# transponder-9_3_0.net
KiCad netlist of a schematic drawn in EAGLE
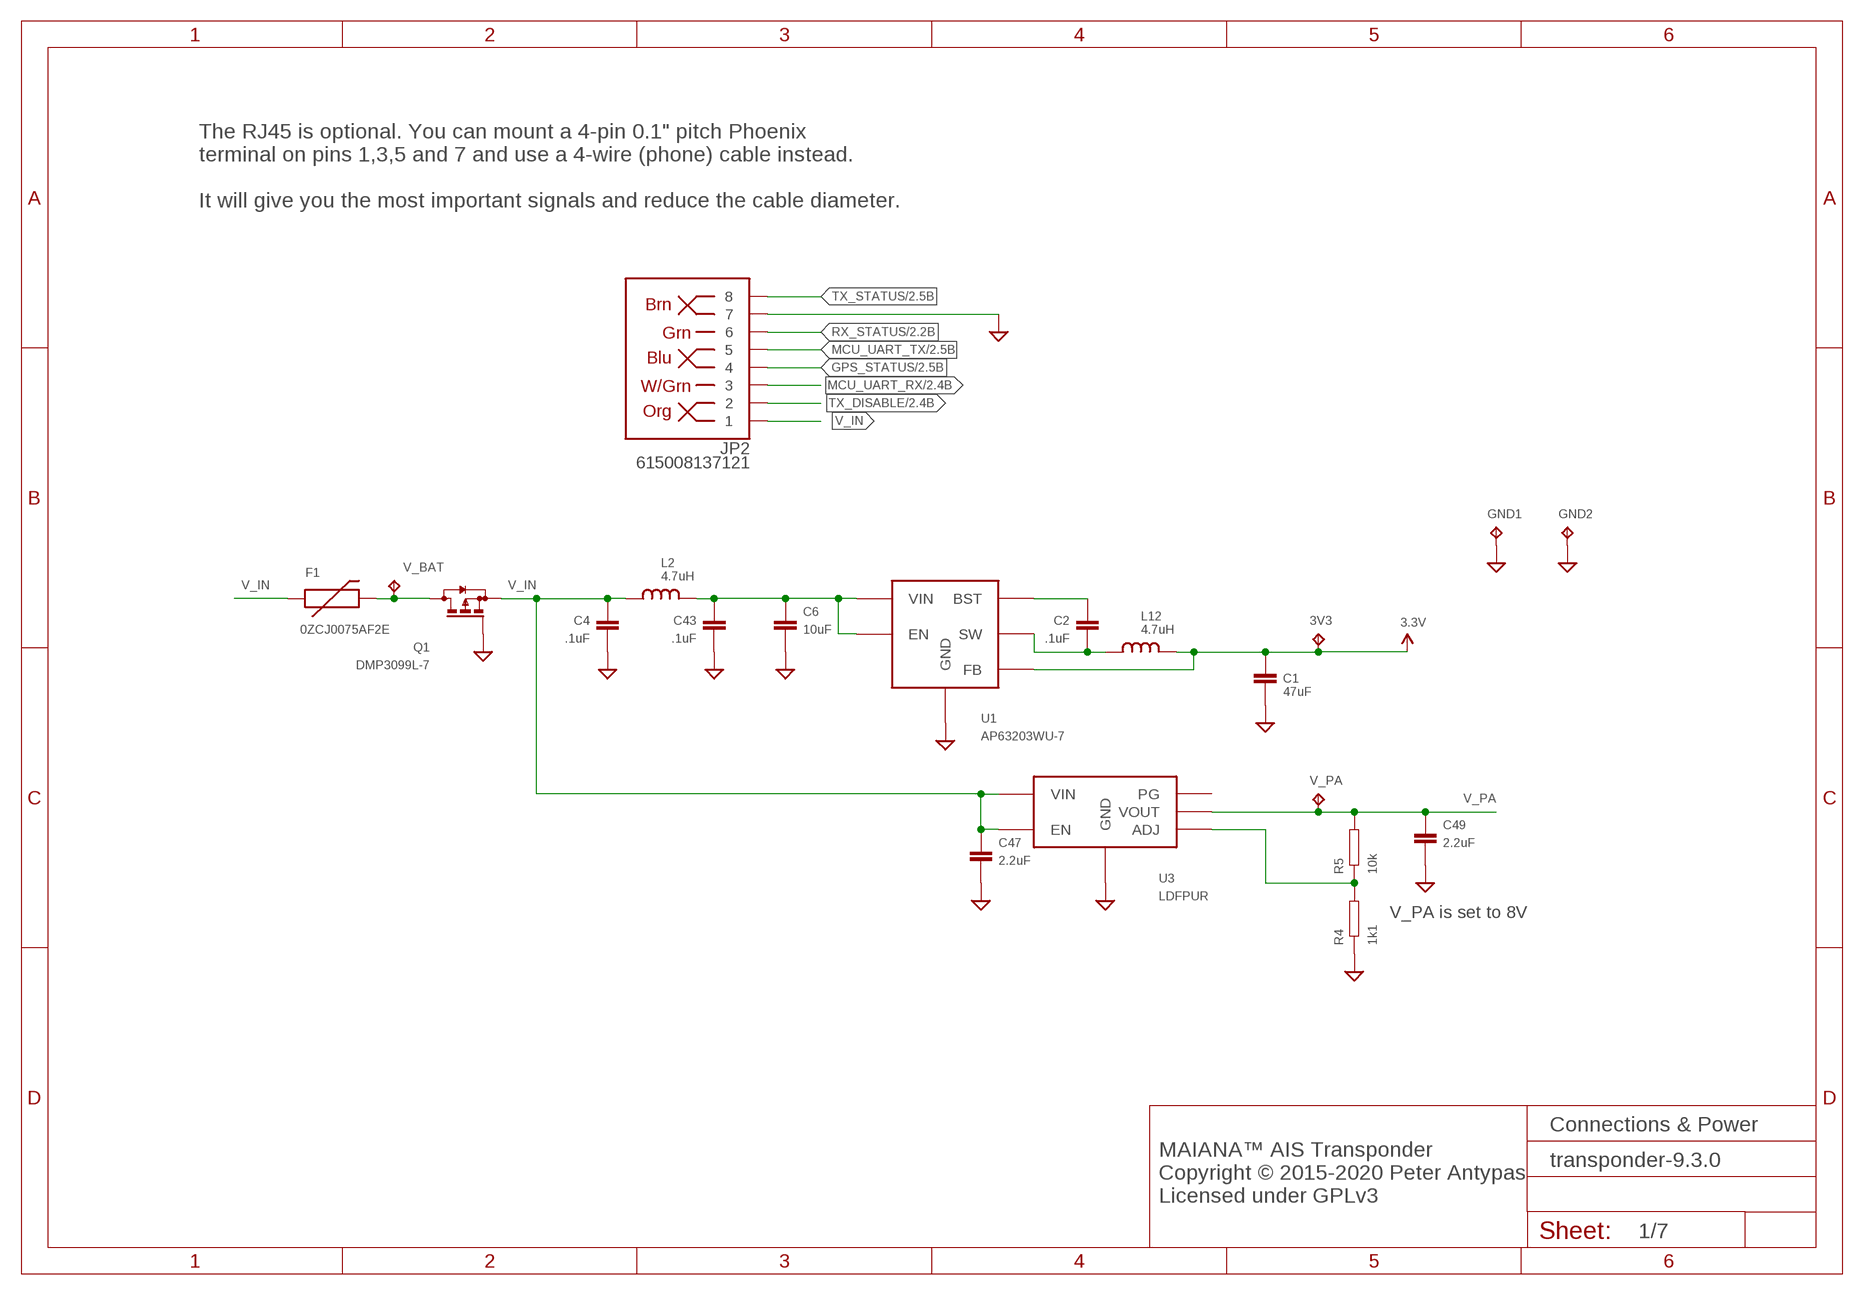
[diagram p0: schematic, sheet 1]
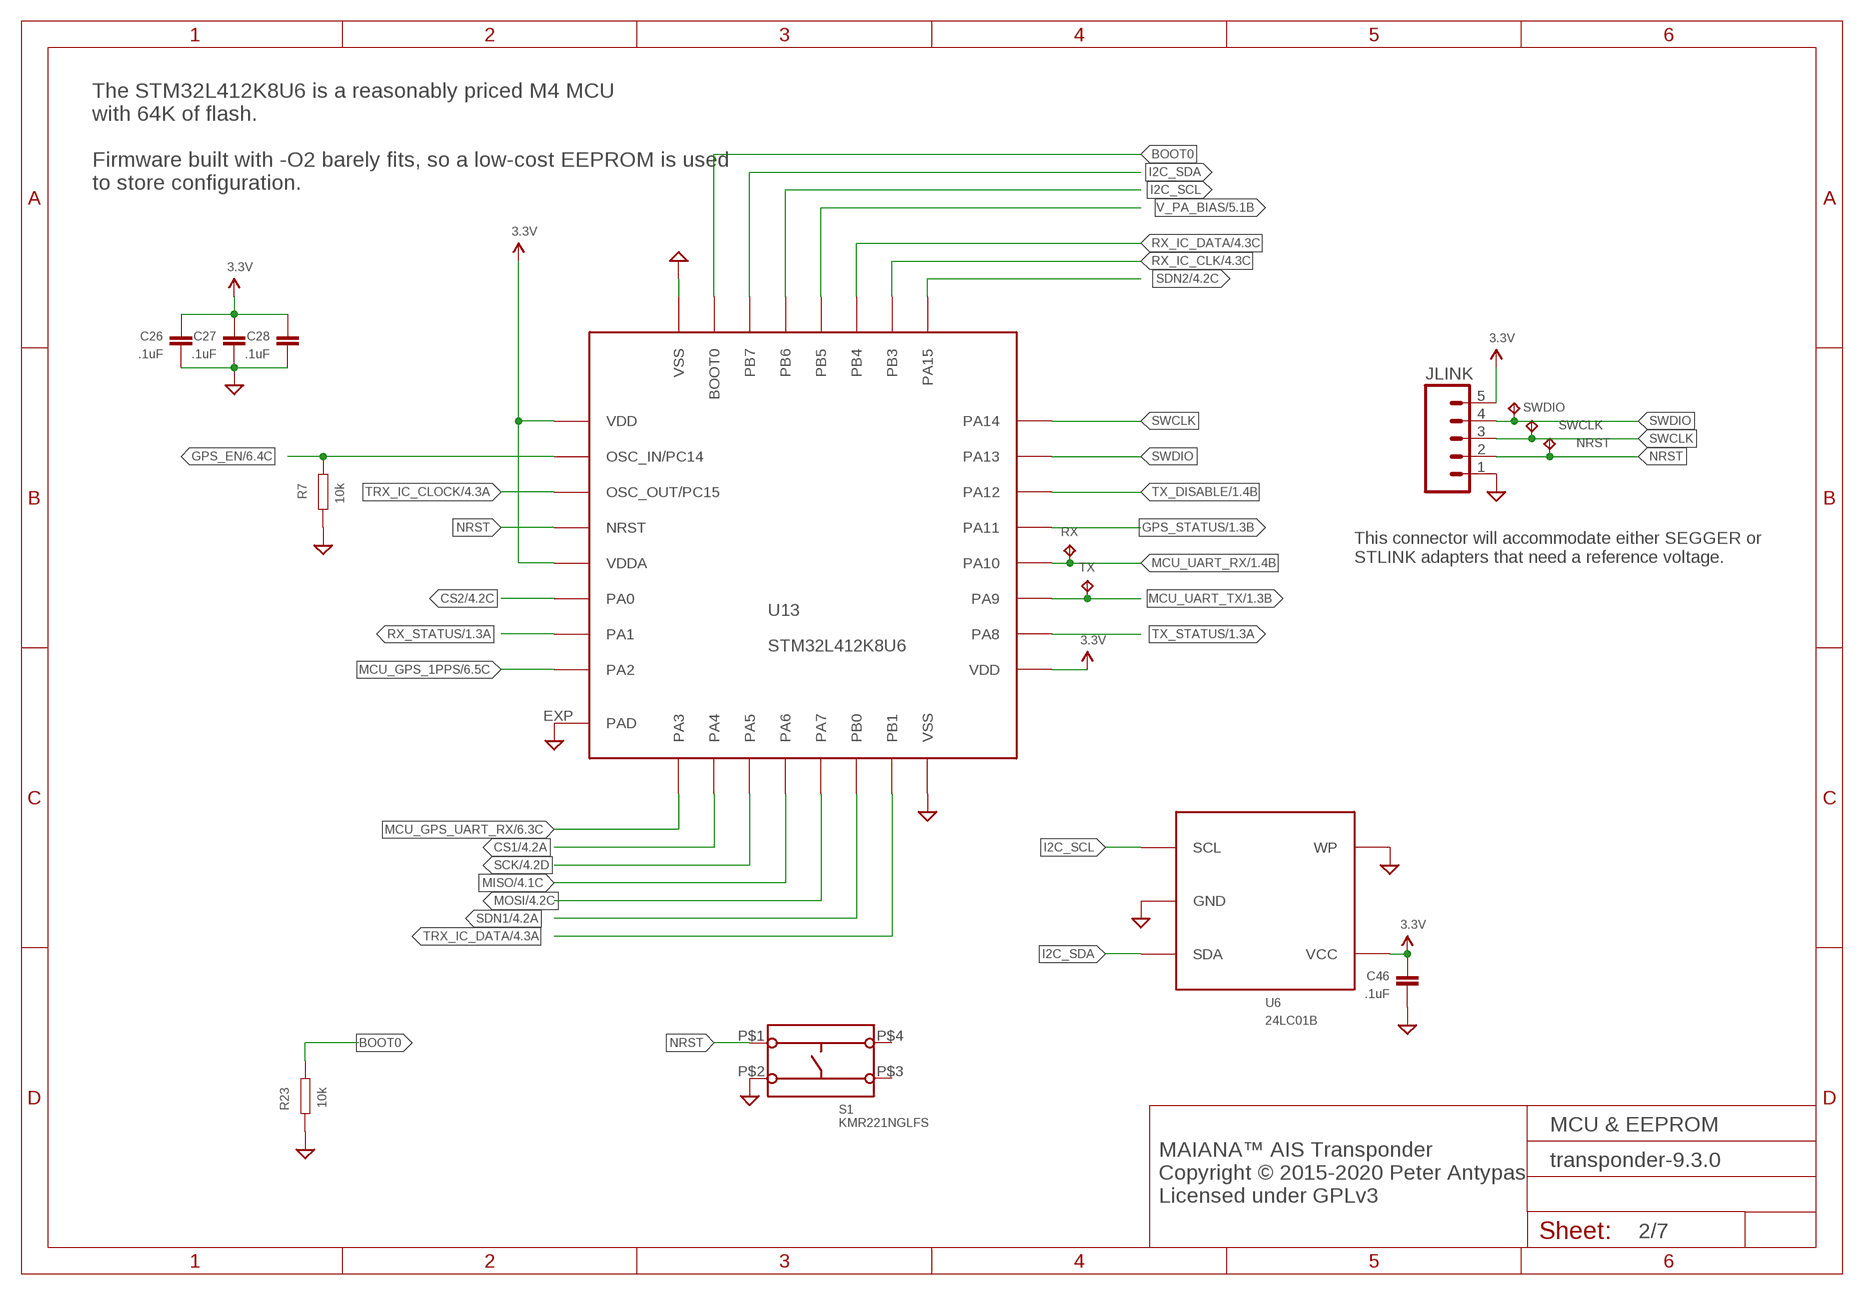
[diagram p1: schematic, sheet 2]
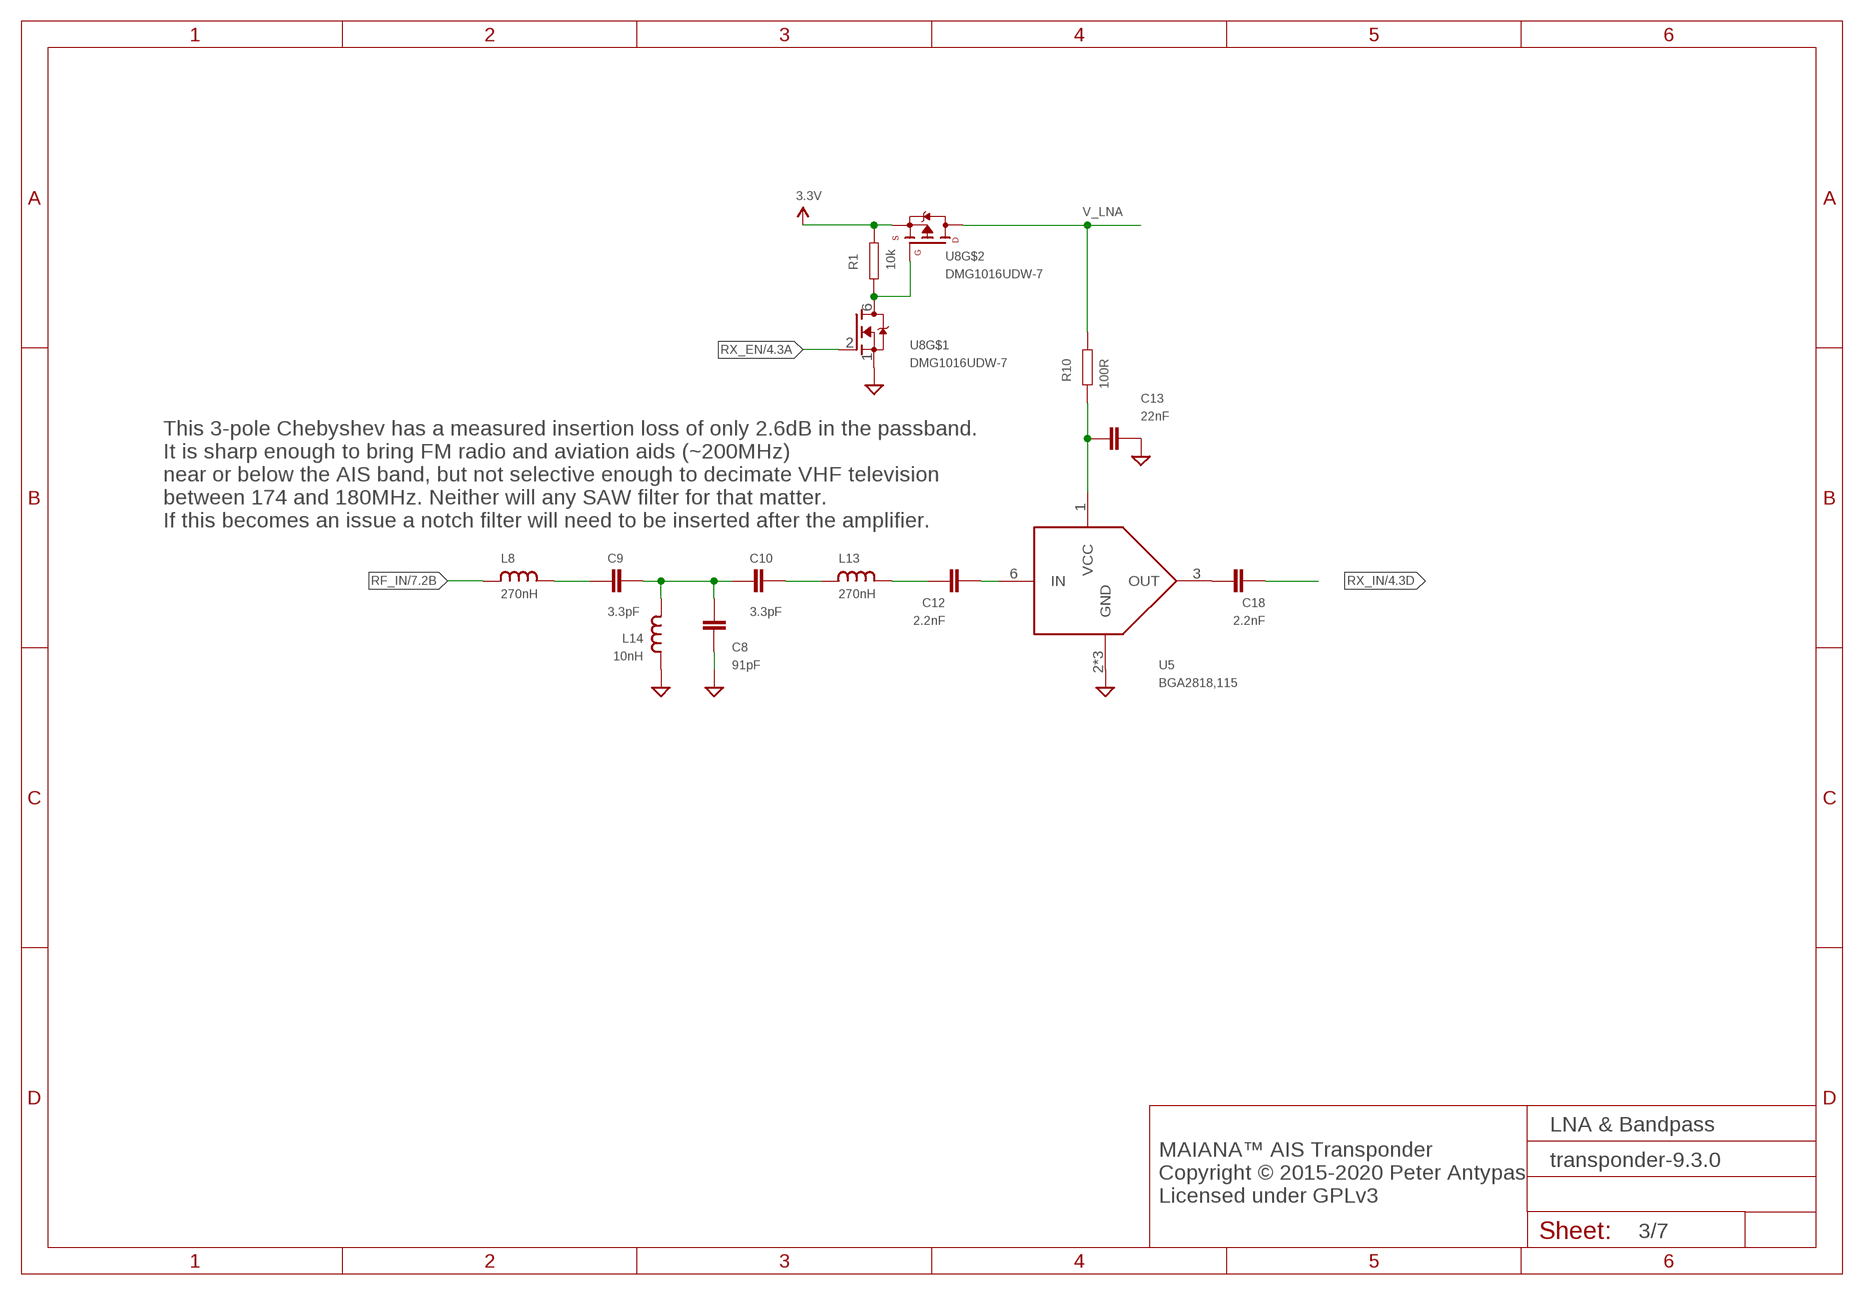
[diagram p2: schematic, sheet 3]
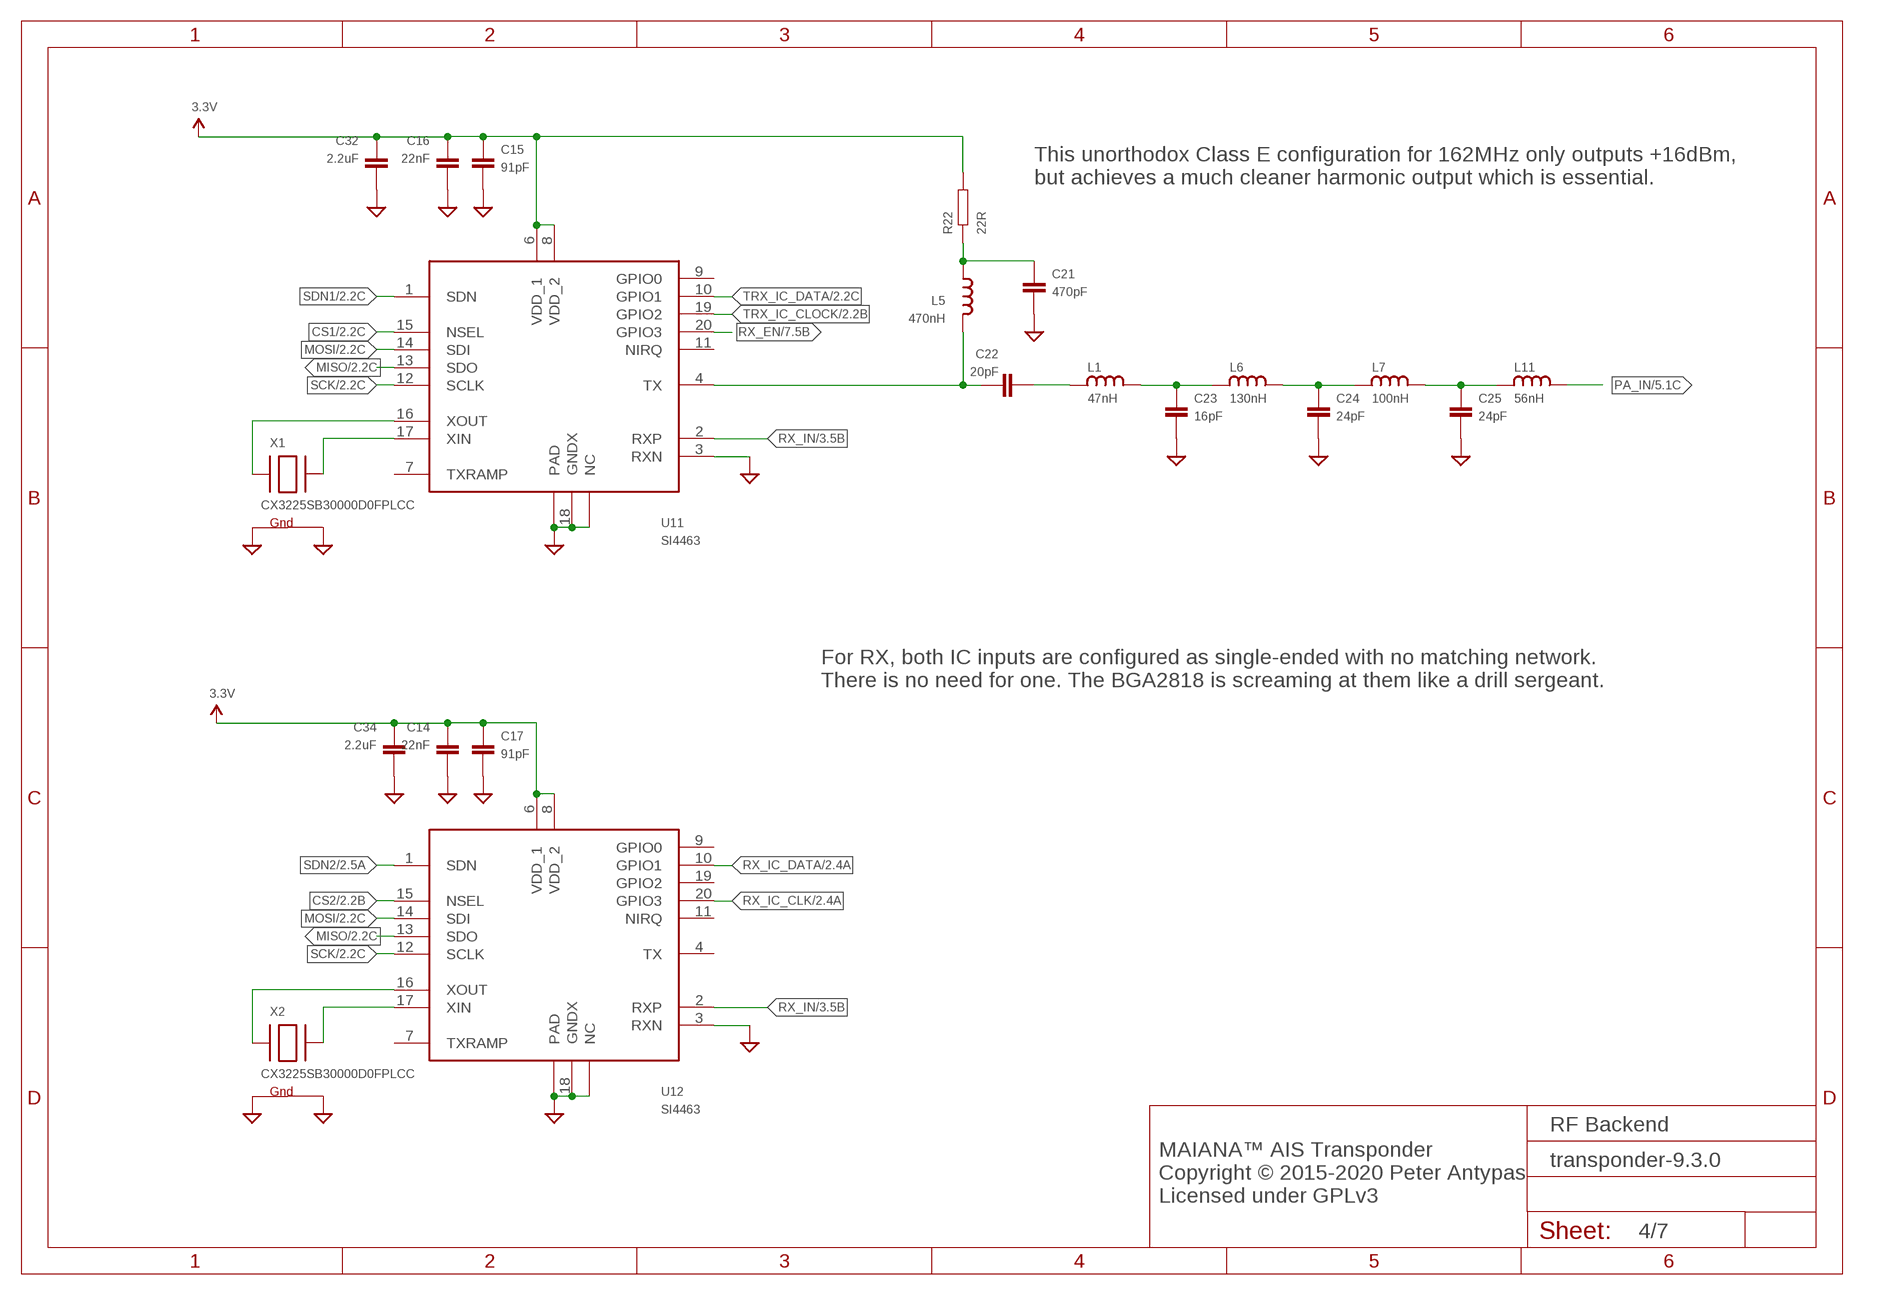
[diagram p3: schematic, sheet 4]
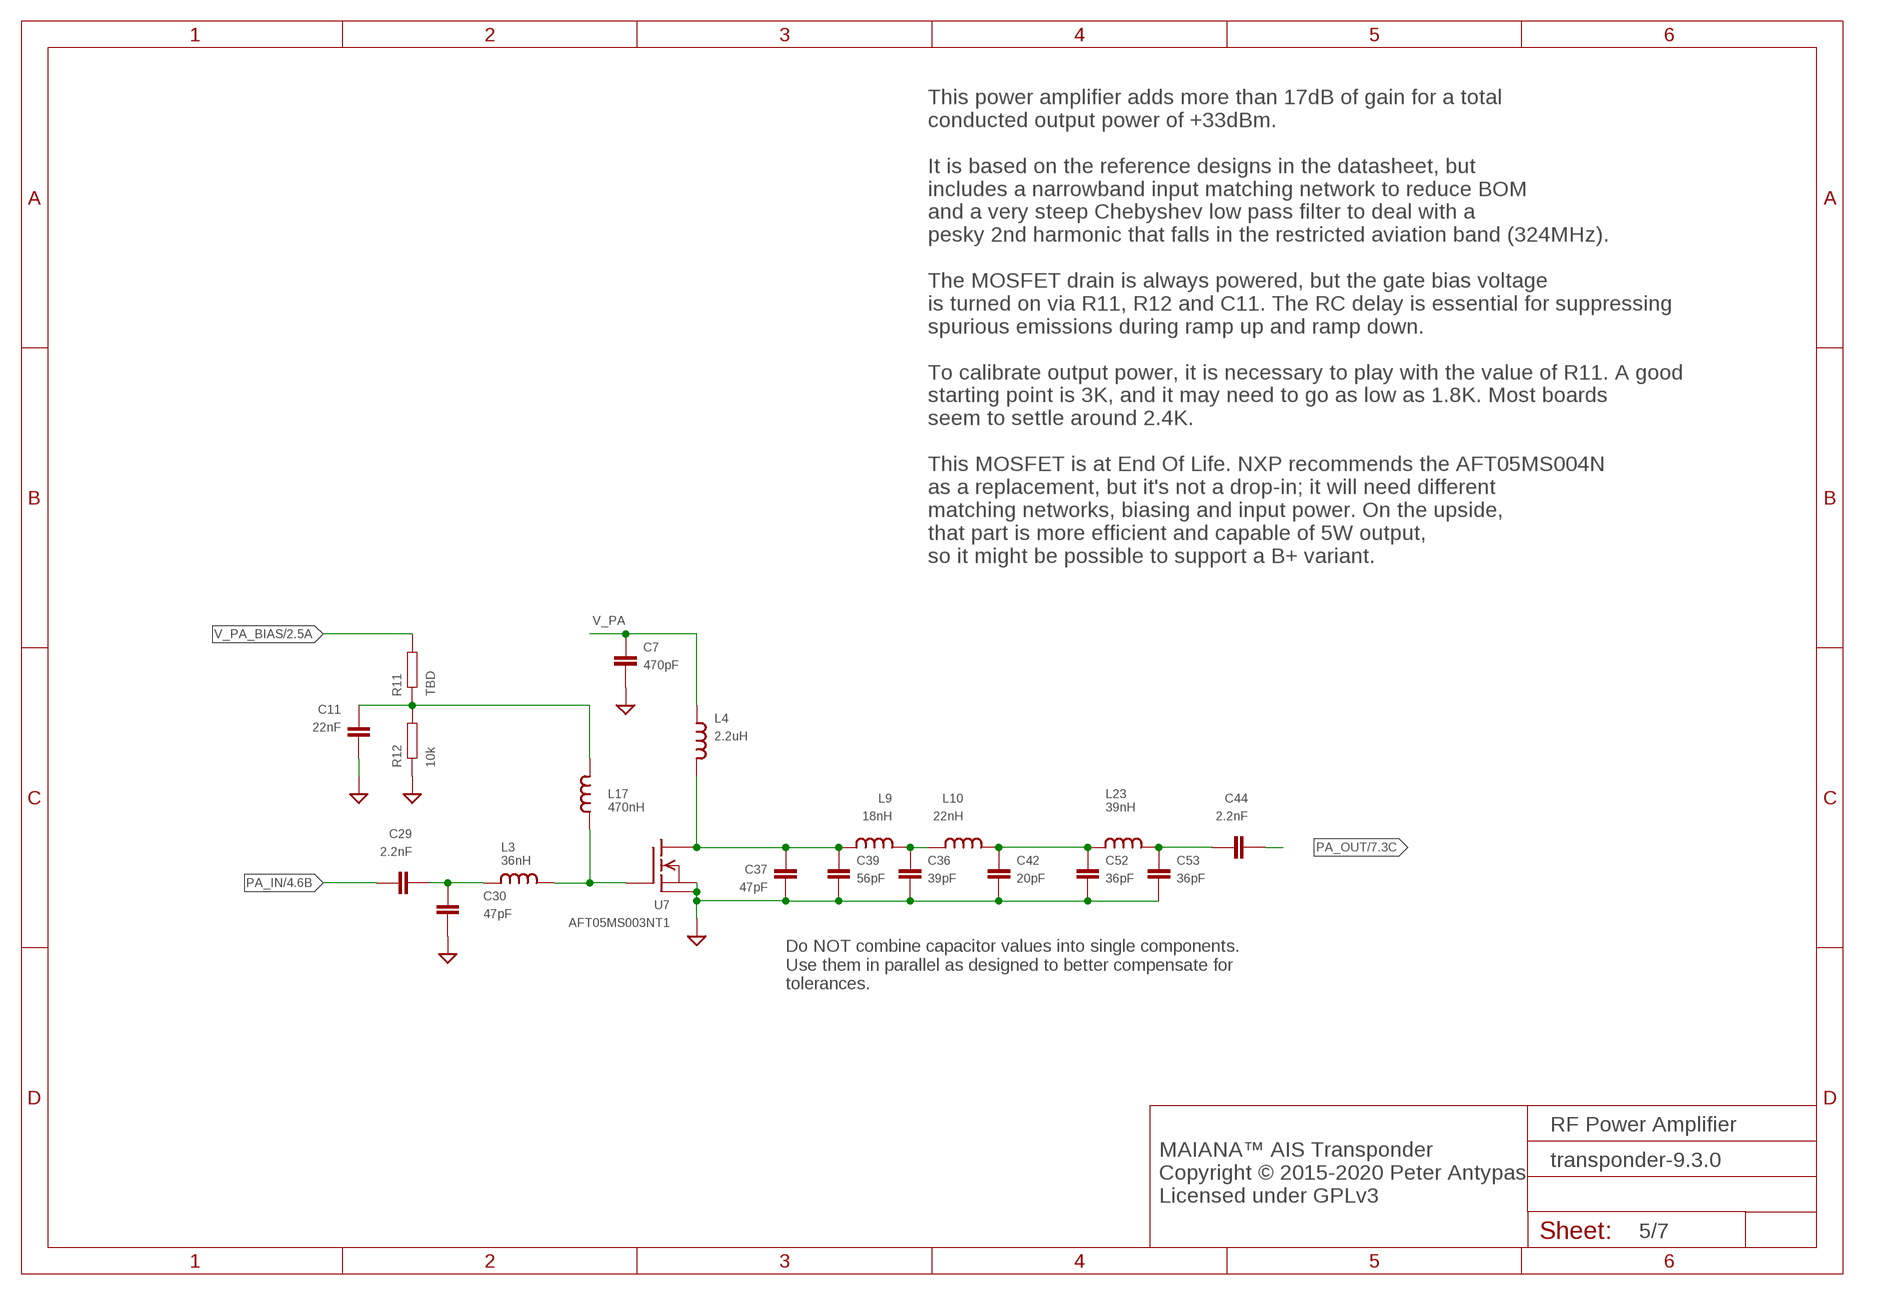
[diagram p4: schematic, sheet 5]
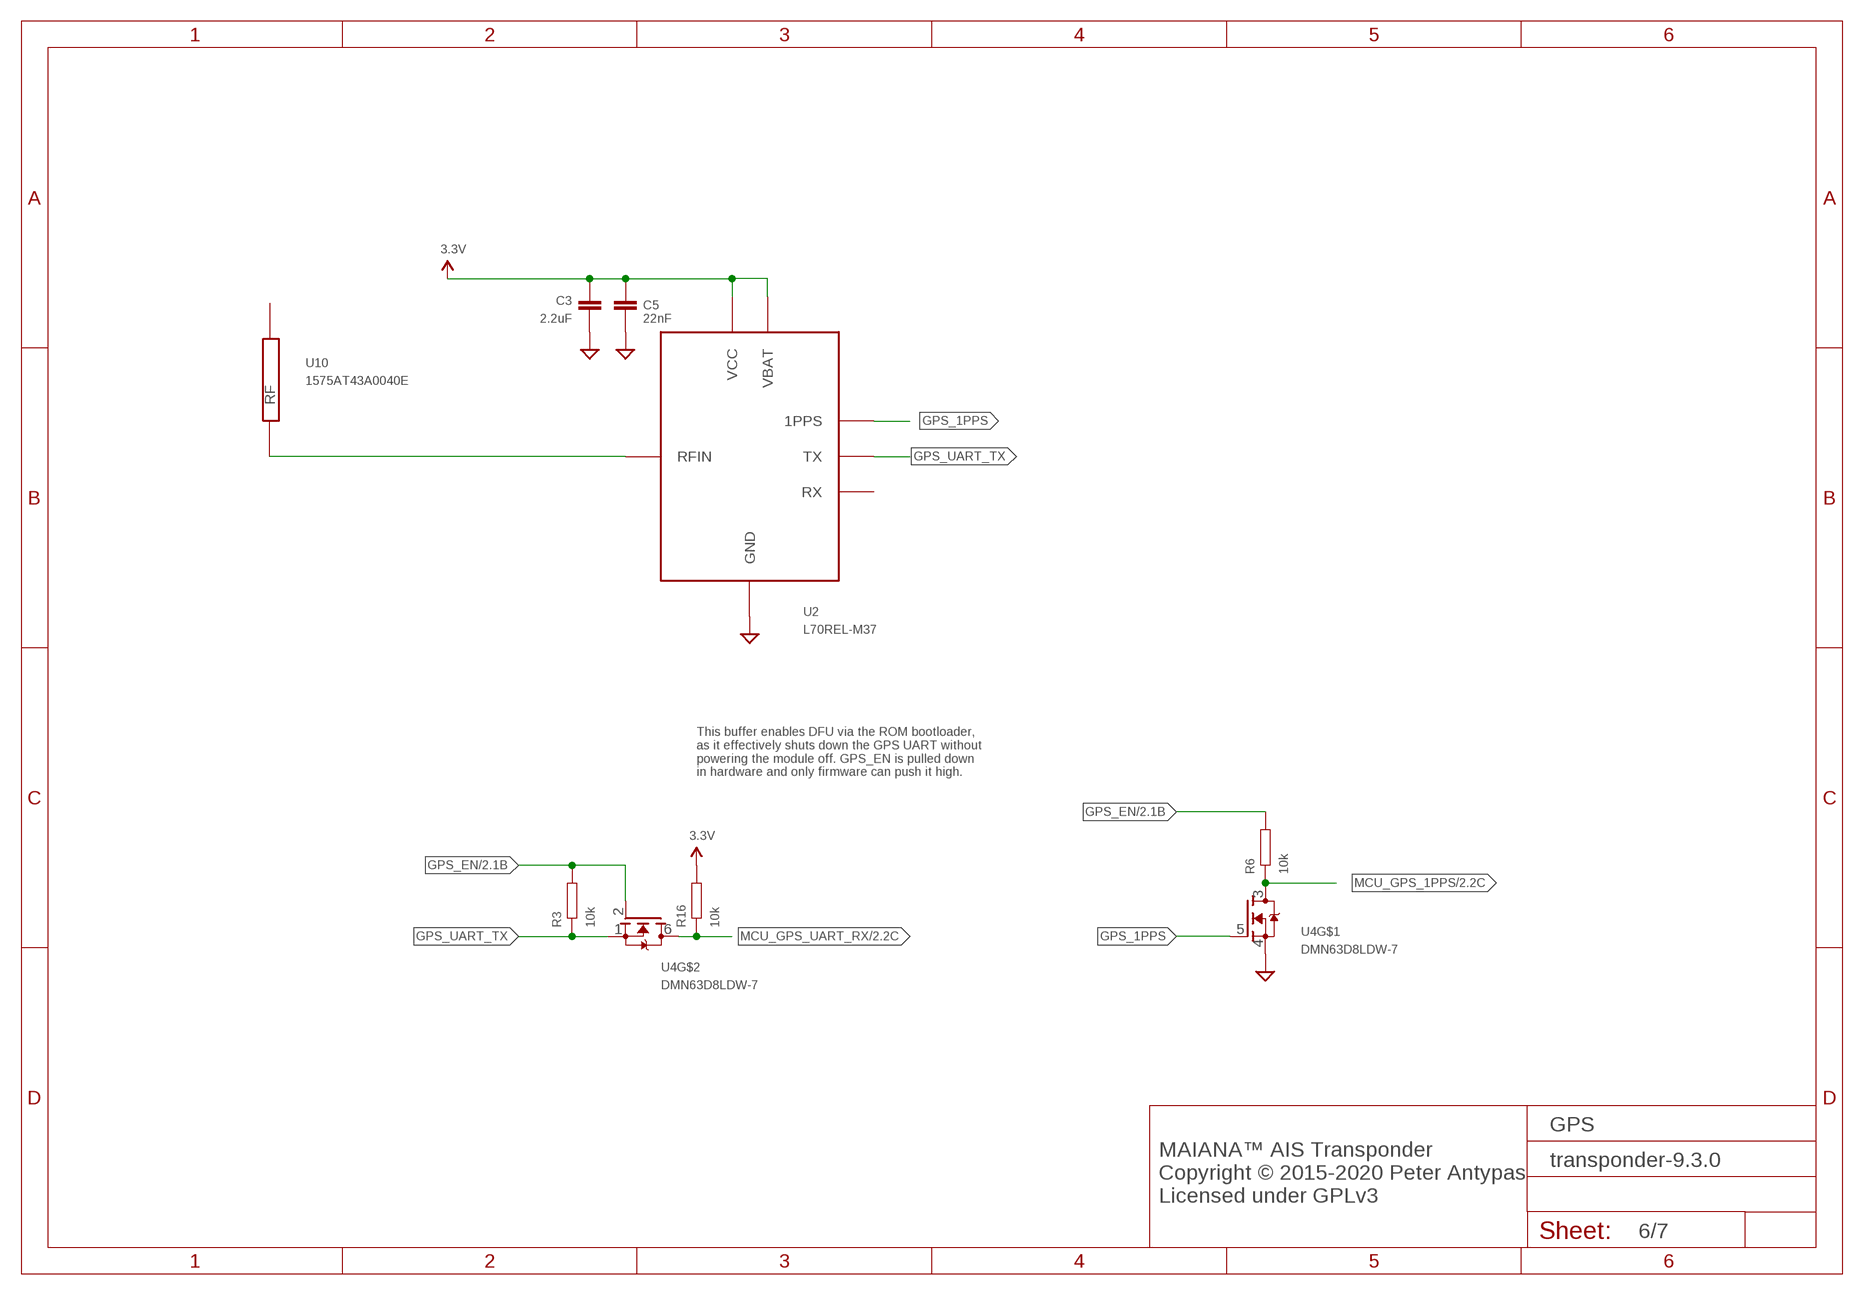
[diagram p5: schematic, sheet 6]
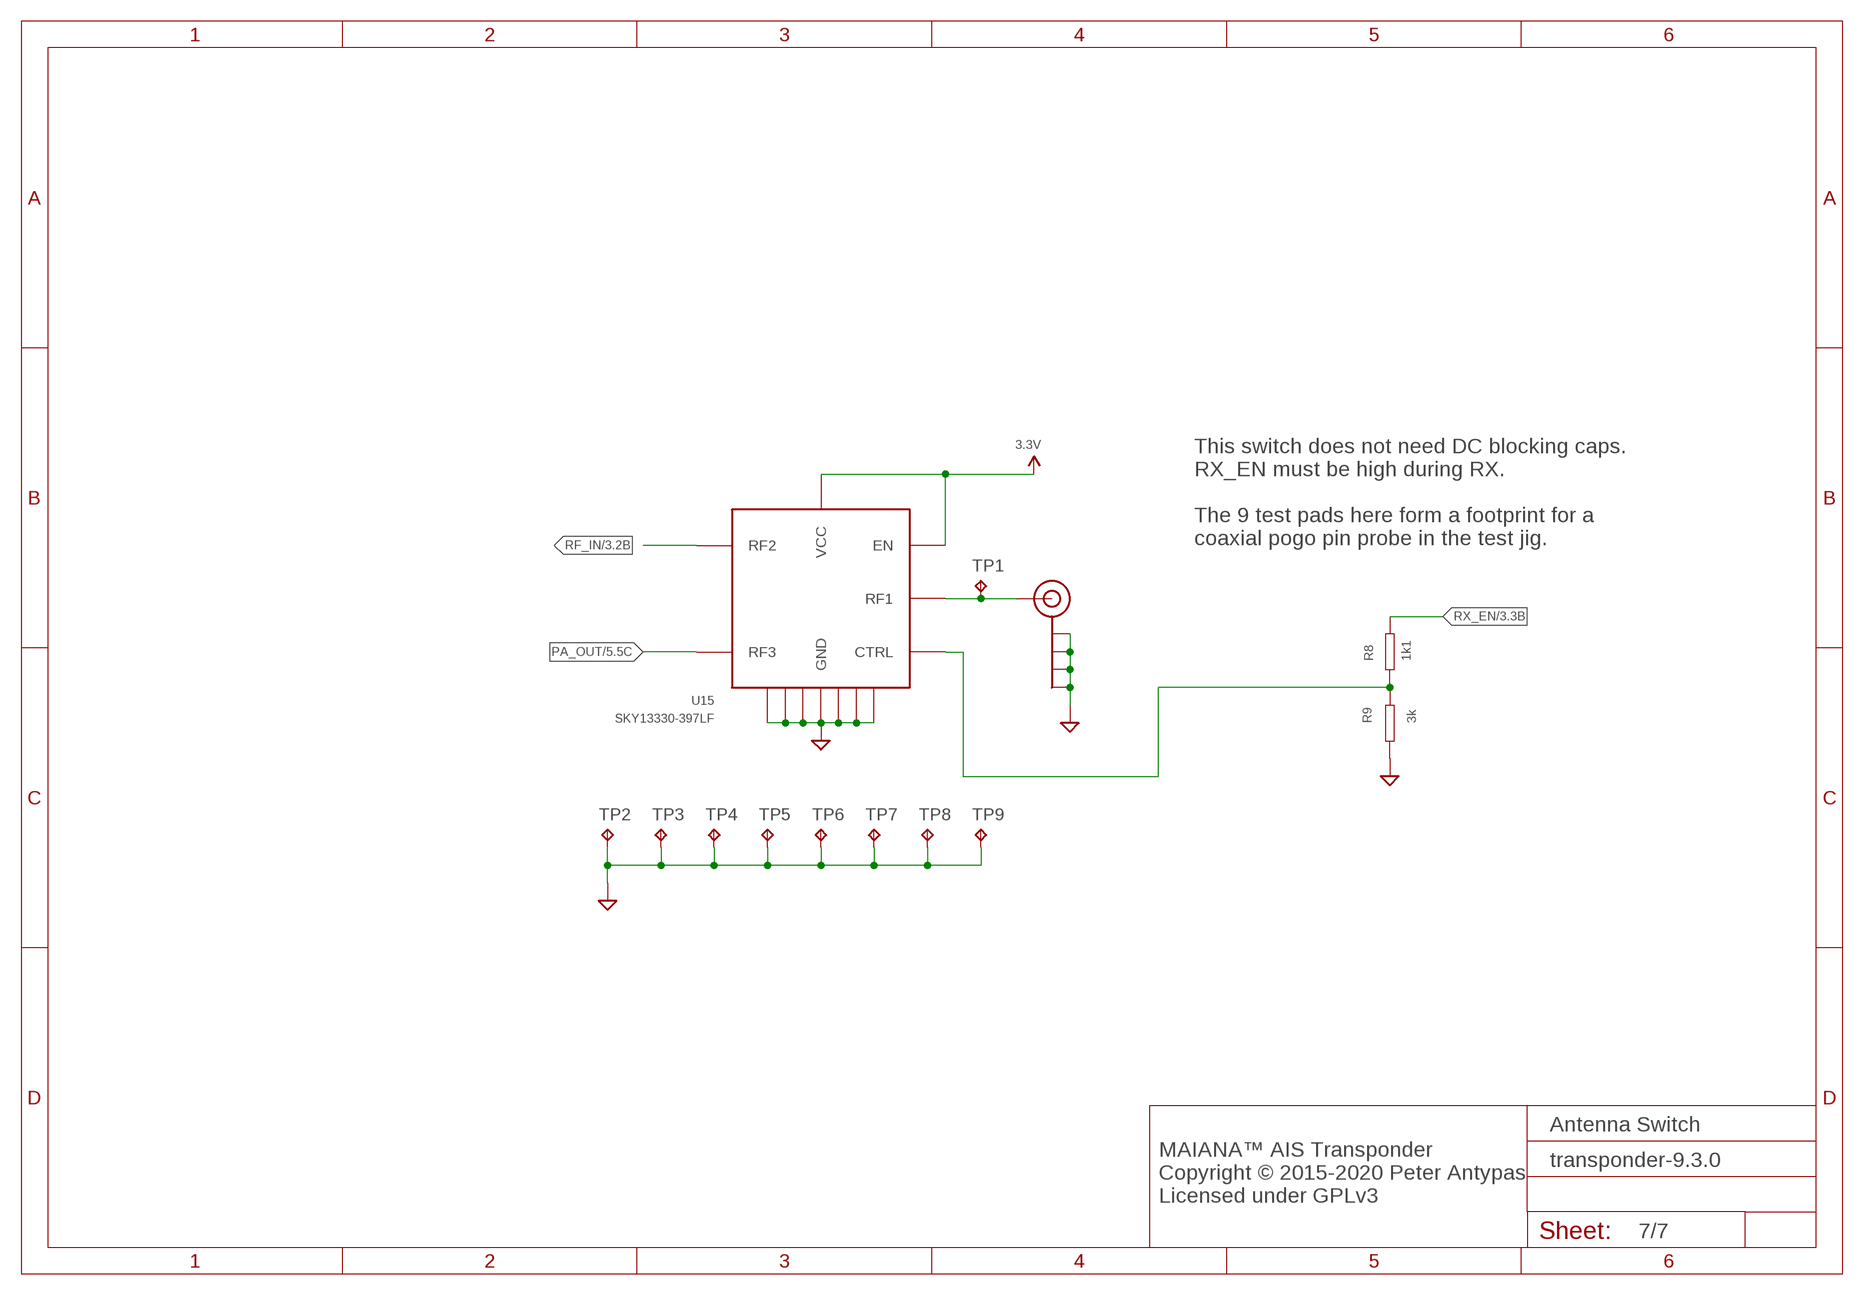
[diagram p6: schematic, sheet 7]

(export (version "E")
  (design (tool "Eeschema 10.0.6"))
  (components
    (comp (ref "C26")
      (value ".1uF")
      (footprint "eagle-import:0603")
      (fields (field (name "PARTNO") "EMK107B7104KAHT"))
      (libsource (lib "eagle-import") (part "CAPACITOR0603"))
    )
    (comp (ref "C27")
      (value ".1uF")
      (footprint "eagle-import:0603")
      (fields (field (name "PARTNO") "EMK107B7104KAHT"))
      (libsource (lib "eagle-import") (part "CAPACITOR0603"))
    )
    (comp (ref "C28")
      (value ".1uF")
      (footprint "eagle-import:0603")
      (fields (field (name "PARTNO") "EMK107B7104KAHT"))
      (libsource (lib "eagle-import") (part "CAPACITOR0603"))
    )
    (comp (ref "C46")
      (value ".1uF")
      (footprint "eagle-import:0603")
      (fields (field (name "PARTNO") "EMK107B7104KAHT"))
      (libsource (lib "eagle-import") (part "CAPACITOR0603"))
    )
    (comp (ref "JLINK")
      (value "M05PTH")
      (footprint "eagle-import:1X05")
      (libsource (lib "eagle-import") (part "M05PTH"))
    )
    (comp (ref "NRST")
      (value "TPTP12R")
      (footprint "eagle-import:TP12R")
      (libsource (lib "eagle-import") (part "TPTP12R"))
    )
    (comp (ref "R7")
      (value "10k")
      (footprint "eagle-import:0603")
      (fields (field (name "PARTNO") "RC0603JR-0710KL"))
      (libsource (lib "eagle-import") (part "RESISTOR0603"))
    )
    (comp (ref "R23")
      (value "10k")
      (footprint "eagle-import:0603")
      (fields (field (name "PARTNO") "RC0603JR-0710KL"))
      (libsource (lib "eagle-import") (part "RESISTOR0603"))
    )
    (comp (ref "RX")
      (value "TPTP12R")
      (footprint "eagle-import:TP12R")
      (libsource (lib "eagle-import") (part "TPTP12R"))
    )
    (comp (ref "S1")
      (value "KMR221NGLFS")
      (footprint "eagle-import:KMR221NGLFS")
      (libsource (lib "eagle-import") (part "KMR221NGLFS"))
    )
    (comp (ref "SWCLK")
      (value "TPTP12R")
      (footprint "eagle-import:TP12R")
      (libsource (lib "eagle-import") (part "TPTP12R"))
    )
    (comp (ref "SWDIO")
      (value "TPTP12R")
      (footprint "eagle-import:TP12R")
      (libsource (lib "eagle-import") (part "TPTP12R"))
    )
    (comp (ref "TX")
      (value "TPTP12R")
      (footprint "eagle-import:TP12R")
      (libsource (lib "eagle-import") (part "TPTP12R"))
    )
    (comp (ref "U6")
      (value "24LC01B")
      (footprint "eagle-import:SOT23-5")
      (fields (field (name "PARTNO") "24LC01BT-I/OT"))
      (libsource (lib "eagle-import") (part "24LC01B"))
    )
    (comp (ref "U13")
      (value "STM32L412K8U6")
      (footprint "eagle-import:QFN32")
      (libsource (lib "eagle-import") (part "STM32L432KXXX"))
    )
    (comp (ref "J$1")
      (value "SMA_EDGE")
      (footprint "eagle-import:SMA-EDGE")
      (libsource (lib "eagle-import") (part "SMA_EDGE"))
    )
    (comp (ref "R8")
      (value "1k1")
      (footprint "eagle-import:0603")
      (fields (field (name "PARTNO") "RC0603JR-071K1L"))
      (libsource (lib "eagle-import") (part "RESISTOR0603"))
    )
    (comp (ref "R9")
      (value "3k")
      (footprint "eagle-import:0603")
      (fields (field (name "PARTNO") "RC0603JR-073KL"))
      (libsource (lib "eagle-import") (part "RESISTOR0603"))
    )
    (comp (ref "TP1")
      (value "TPTP10R")
      (footprint "eagle-import:TP10R")
      (libsource (lib "eagle-import") (part "TPTP10R"))
    )
    (comp (ref "TP2")
      (value "TPTP08R")
      (footprint "eagle-import:TP08R")
      (libsource (lib "eagle-import") (part "TPTP08R"))
    )
    (comp (ref "TP3")
      (value "TPTP08R")
      (footprint "eagle-import:TP08R")
      (libsource (lib "eagle-import") (part "TPTP08R"))
    )
    (comp (ref "TP4")
      (value "TPTP08R")
      (footprint "eagle-import:TP08R")
      (libsource (lib "eagle-import") (part "TPTP08R"))
    )
    (comp (ref "TP5")
      (value "TPTP08R")
      (footprint "eagle-import:TP08R")
      (libsource (lib "eagle-import") (part "TPTP08R"))
    )
    (comp (ref "TP6")
      (value "TPTP08R")
      (footprint "eagle-import:TP08R")
      (libsource (lib "eagle-import") (part "TPTP08R"))
    )
    (comp (ref "TP7")
      (value "TPTP08R")
      (footprint "eagle-import:TP08R")
      (libsource (lib "eagle-import") (part "TPTP08R"))
    )
    (comp (ref "TP8")
      (value "TPTP08R")
      (footprint "eagle-import:TP08R")
      (libsource (lib "eagle-import") (part "TPTP08R"))
    )
    (comp (ref "TP9")
      (value "TPTP08R")
      (footprint "eagle-import:TP08R")
      (libsource (lib "eagle-import") (part "TPTP08R"))
    )
    (comp (ref "U15")
      (value "SKY13330-397LF")
      (footprint "eagle-import:QFN12")
      (libsource (lib "eagle-import") (part "SKYWORKS-13330397LF"))
    )
    (comp (ref "C3")
      (value "2.2uF")
      (footprint "eagle-import:0603")
      (fields (field (name "PARTNO") "EMK107BJ225KA-T"))
      (libsource (lib "eagle-import") (part "CAPACITOR0603"))
    )
    (comp (ref "C5")
      (value "22nF")
      (footprint "eagle-import:0603")
      (fields (field (name "PARTNO") "GRM188R71E223KA01D"))
      (libsource (lib "eagle-import") (part "CAPACITOR0603"))
    )
    (comp (ref "R3")
      (value "10k")
      (footprint "eagle-import:0603")
      (fields (field (name "PARTNO") "RC0603JR-0710KL"))
      (libsource (lib "eagle-import") (part "RESISTOR0603"))
    )
    (comp (ref "R6")
      (value "10k")
      (footprint "eagle-import:0603")
      (fields (field (name "PARTNO") "RC0603JR-0710KL"))
      (libsource (lib "eagle-import") (part "RESISTOR0603"))
    )
    (comp (ref "R16")
      (value "10k")
      (footprint "eagle-import:0603")
      (fields (field (name "PARTNO") "RC0603JR-0710KL"))
      (libsource (lib "eagle-import") (part "RESISTOR0603"))
    )
    (comp (ref "U2")
      (value "L70REL-M37")
      (footprint "eagle-import:GPS_MODULE")
      (fields (field (name "PARTNO") "L70B-M39"))
      (libsource (lib "eagle-import") (part "L70"))
    )
    (comp (ref "U4")
      (value "DMN63D8LDW-7")
      (footprint "eagle-import:SOT363")
      (fields (field (name "PARTNO") "DMN63D8LDW-7"))
      (libsource (lib "eagle-import") (part "DMN63D8LDW"))
    )
    (comp (ref "U10")
      (value "1575AT43A0040E")
      (footprint "eagle-import:1575AT43A0040E")
      (libsource (lib "eagle-import") (part "1575AT43A0040E"))
    )
    (comp (ref "C8")
      (value "91pF")
      (footprint "eagle-import:0603")
      (fields (field (name "PARTNO") "GRM1885C2A910JA01D"))
      (libsource (lib "eagle-import") (part "CAPACITOR0603"))
    )
    (comp (ref "C9")
      (value "3.3pF")
      (footprint "eagle-import:0603")
      (fields (field (name "PARTNO") "GRM1885C1H3R3BA01D"))
      (libsource (lib "eagle-import") (part "CAPACITOR0603"))
    )
    (comp (ref "C10")
      (value "3.3pF")
      (footprint "eagle-import:0603")
      (fields (field (name "PARTNO") "GRM1885C1H3R3BA01D"))
      (libsource (lib "eagle-import") (part "CAPACITOR0603"))
    )
    (comp (ref "C12")
      (value "2.2nF")
      (footprint "eagle-import:0603")
      (fields (field (name "PARTNO") "GRM1885C1H222JA01J"))
      (libsource (lib "eagle-import") (part "CAPACITOR0603"))
    )
    (comp (ref "C13")
      (value "22nF")
      (footprint "eagle-import:0603")
      (fields (field (name "PARTNO") "GRM188R71E223KA01D"))
      (libsource (lib "eagle-import") (part "CAPACITOR0603"))
    )
    (comp (ref "C18")
      (value "2.2nF")
      (footprint "eagle-import:0603")
      (fields (field (name "PARTNO") "GRM1885C1H222JA01J"))
      (libsource (lib "eagle-import") (part "CAPACITOR0603"))
    )
    (comp (ref "L8")
      (value "270nH")
      (footprint "eagle-import:0603")
      (fields (field (name "PARTNO") "LQW18ANR27J00D"))
      (libsource (lib "eagle-import") (part "INDUCTOR0603"))
    )
    (comp (ref "L13")
      (value "270nH")
      (footprint "eagle-import:0603")
      (fields (field (name "PARTNO") "LQW18ANR27J00D"))
      (libsource (lib "eagle-import") (part "INDUCTOR0603"))
    )
    (comp (ref "L14")
      (value "10nH")
      (footprint "eagle-import:0603")
      (fields (field (name "PARTNO") "LQW18AN10NG00D"))
      (libsource (lib "eagle-import") (part "INDUCTOR0603"))
    )
    (comp (ref "R1")
      (value "10k")
      (footprint "eagle-import:0603")
      (fields (field (name "PARTNO") "RC0603JR-0710KL"))
      (libsource (lib "eagle-import") (part "RESISTOR0603"))
    )
    (comp (ref "R10")
      (value "100R")
      (footprint "eagle-import:0603")
      (fields (field (name "PARTNO") "RC0603JR-07100RL"))
      (libsource (lib "eagle-import") (part "RESISTOR0603"))
    )
    (comp (ref "U5")
      (value "BGA2818,115")
      (footprint "eagle-import:SOT363")
      (libsource (lib "eagle-import") (part "BGA2870"))
    )
    (comp (ref "U8")
      (value "DMG1016UDW-7")
      (footprint "eagle-import:SOT363")
      (libsource (lib "eagle-import") (part "DMG1016UDW"))
    )
    (comp (ref "C7")
      (value "470pF")
      (footprint "eagle-import:0603")
      (fields (field (name "PARTNO") "GRM1885C1H471JA01D"))
      (libsource (lib "eagle-import") (part "CAPACITOR0603"))
    )
    (comp (ref "C11")
      (value "22nF")
      (footprint "eagle-import:0603")
      (fields (field (name "PARTNO") "GRM188R71E223KA01D"))
      (libsource (lib "eagle-import") (part "CAPACITOR0603"))
    )
    (comp (ref "C29")
      (value "2.2nF")
      (footprint "eagle-import:0603")
      (fields (field (name "PARTNO") "GRM1885C1H222JA01J"))
      (libsource (lib "eagle-import") (part "CAPACITOR0603"))
    )
    (comp (ref "C30")
      (value "47pF")
      (footprint "eagle-import:0603")
      (fields (field (name "PARTNO") "GRM1885C1H470JA01J"))
      (libsource (lib "eagle-import") (part "CAPACITOR0603"))
    )
    (comp (ref "C36")
      (value "39pF")
      (footprint "eagle-import:0603")
      (fields (field (name "PARTNO") "GRM1885C1H390JA01D"))
      (libsource (lib "eagle-import") (part "CAPACITOR0603"))
    )
    (comp (ref "C37")
      (value "47pF")
      (footprint "eagle-import:0603")
      (fields (field (name "PARTNO") "GRM1885C1H470JA01J"))
      (libsource (lib "eagle-import") (part "CAPACITOR0603"))
    )
    (comp (ref "C39")
      (value "56pF")
      (footprint "eagle-import:0603")
      (fields (field (name "PARTNO") "GRM1885C1H560JA01D"))
      (libsource (lib "eagle-import") (part "CAPACITOR0603"))
    )
    (comp (ref "C42")
      (value "20pF")
      (footprint "eagle-import:0603")
      (fields (field (name "PARTNO") "GRM1885C1H200JA01D"))
      (libsource (lib "eagle-import") (part "CAPACITOR0603"))
    )
    (comp (ref "C44")
      (value "2.2nF")
      (footprint "eagle-import:0603")
      (fields (field (name "PARTNO") "GRM1885C1H222JA01J"))
      (libsource (lib "eagle-import") (part "CAPACITOR0603"))
    )
    (comp (ref "C52")
      (value "36pF")
      (footprint "eagle-import:0603")
      (fields (field (name "PARTNO") "06035A360JAT2A"))
      (libsource (lib "eagle-import") (part "CAPACITOR0603"))
    )
    (comp (ref "C53")
      (value "36pF")
      (footprint "eagle-import:0603")
      (fields (field (name "PARTNO") "06035A360JAT2A"))
      (libsource (lib "eagle-import") (part "CAPACITOR0603"))
    )
    (comp (ref "L3")
      (value "36nH")
      (footprint "eagle-import:0603")
      (fields (field (name "PARTNO") "LQW18AN36NG00D"))
      (libsource (lib "eagle-import") (part "INDUCTOR0603"))
    )
    (comp (ref "L4")
      (value "2.2uH")
      (footprint "eagle-import:0805")
      (fields (field (name "PARTNO") "BRC2012T2R2MD"))
      (libsource (lib "eagle-import") (part "INDUCTOR0805"))
    )
    (comp (ref "L9")
      (value "18nH")
      (footprint "eagle-import:0603")
      (fields (field (name "PARTNO") "LQW18AN18NG00D"))
      (libsource (lib "eagle-import") (part "INDUCTOR0603"))
    )
    (comp (ref "L10")
      (value "22nH")
      (footprint "eagle-import:0603")
      (fields (field (name "PARTNO") "LQW18AN22NJ00D"))
      (libsource (lib "eagle-import") (part "INDUCTOR0603"))
    )
    (comp (ref "L17")
      (value "470nH")
      (footprint "eagle-import:0603")
      (fields (field (name "PARTNO") "HK1608R47J-T"))
      (libsource (lib "eagle-import") (part "INDUCTOR0603"))
    )
    (comp (ref "L23")
      (value "39nH")
      (footprint "eagle-import:0603")
      (fields (field (name "PARTNO") "LQW18AN39NG00D"))
      (libsource (lib "eagle-import") (part "INDUCTOR0603"))
    )
    (comp (ref "R11")
      (value "TBD")
      (footprint "eagle-import:0603")
      (libsource (lib "eagle-import") (part "RESISTOR0603"))
    )
    (comp (ref "R12")
      (value "10k")
      (footprint "eagle-import:0603")
      (fields (field (name "PARTNO") "RC0603JR-0710KL"))
      (libsource (lib "eagle-import") (part "RESISTOR0603"))
    )
    (comp (ref "U7")
      (value "AFT05MS003NT1")
      (footprint "eagle-import:SOT-89")
      (libsource (lib "eagle-import") (part "AFT0SMS003N"))
    )
    (comp (ref "3V3")
      (value "TPTP12R")
      (footprint "eagle-import:TP12R")
      (libsource (lib "eagle-import") (part "TPTP12R"))
    )
    (comp (ref "C1")
      (value "47uF")
      (footprint "eagle-import:1206")
      (fields (field (name "PARTNO") "CL31A476MQHNNNE"))
      (libsource (lib "eagle-import") (part "CAPACITOR1206"))
    )
    (comp (ref "C2")
      (value ".1uF")
      (footprint "eagle-import:0603")
      (fields (field (name "PARTNO") "EMK107B7104KAHT"))
      (libsource (lib "eagle-import") (part "CAPACITOR0603"))
    )
    (comp (ref "C4")
      (value ".1uF")
      (footprint "eagle-import:0603")
      (fields (field (name "PARTNO") "EMK107B7104KAHT"))
      (libsource (lib "eagle-import") (part "CAPACITOR0603"))
    )
    (comp (ref "C6")
      (value "10uF")
      (footprint "eagle-import:0805")
      (fields (field (name "PARTNO") " EMK212ABJ106KG-T"))
      (libsource (lib "eagle-import") (part "CAPACITOR0805"))
    )
    (comp (ref "C43")
      (value ".1uF")
      (footprint "eagle-import:0603")
      (fields (field (name "PARTNO") "EMK107B7104KAHT"))
      (libsource (lib "eagle-import") (part "CAPACITOR0603"))
    )
    (comp (ref "C47")
      (value "2.2uF")
      (footprint "eagle-import:0603")
      (fields (field (name "PARTNO") "EMK107BJ225KA-T"))
      (libsource (lib "eagle-import") (part "CAPACITOR0603"))
    )
    (comp (ref "C49")
      (value "2.2uF")
      (footprint "eagle-import:0603")
      (fields (field (name "PARTNO") "EMK107BJ225KA-T"))
      (libsource (lib "eagle-import") (part "CAPACITOR0603"))
    )
    (comp (ref "F1")
      (value "0ZCJ0075AF2E")
      (footprint "eagle-import:PTC-1206")
      (libsource (lib "eagle-import") (part "PTCSMD"))
    )
    (comp (ref "GND1")
      (value "TPTP16R")
      (footprint "eagle-import:TP16R")
      (libsource (lib "eagle-import") (part "TPTP16R"))
    )
    (comp (ref "GND2")
      (value "TPTP16R")
      (footprint "eagle-import:TP16R")
      (libsource (lib "eagle-import") (part "TPTP16R"))
    )
    (comp (ref "JP2")
      (value "615008137121")
      (footprint "eagle-import:RJ45-8")
      (fields (field (name "PARTNO") "‎615008137121‎"))
      (libsource (lib "eagle-import") (part "RJ45-8PTH"))
    )
    (comp (ref "L2")
      (value "4.7uH")
      (footprint "eagle-import:0805")
      (fields (field (name "PARTNO") "MLZ2012M4R7WT000"))
      (libsource (lib "eagle-import") (part "INDUCTOR0805"))
    )
    (comp (ref "L12")
      (value "4.7uH")
      (footprint "eagle-import:0805")
      (fields (field (name "PARTNO") "MLZ2012M4R7WT000"))
      (libsource (lib "eagle-import") (part "INDUCTOR0805"))
    )
    (comp (ref "Q1")
      (value "DMP3099L-7")
      (footprint "eagle-import:SOT23")
      (libsource (lib "eagle-import") (part "BSS84"))
    )
    (comp (ref "R4")
      (value "1k1")
      (footprint "eagle-import:0603")
      (fields (field (name "PARTNO") "RC0603JR-071K1L"))
      (libsource (lib "eagle-import") (part "RESISTOR0603"))
    )
    (comp (ref "R5")
      (value "10k")
      (footprint "eagle-import:0603")
      (fields (field (name "PARTNO") "RC0603JR-0710KL"))
      (libsource (lib "eagle-import") (part "RESISTOR0603"))
    )
    (comp (ref "U1")
      (value "AP63203WU-7")
      (footprint "eagle-import:SOT23-6")
      (libsource (lib "eagle-import") (part "AP63203"))
    )
    (comp (ref "U3")
      (value "LDFPUR")
      (footprint "eagle-import:DFN-6")
      (libsource (lib "eagle-import") (part "LDF"))
    )
    (comp (ref "V_BAT")
      (value "TPTP12R")
      (footprint "eagle-import:TP12R")
      (libsource (lib "eagle-import") (part "TPTP12R"))
    )
    (comp (ref "V_PA")
      (value "TPTP12R")
      (footprint "eagle-import:TP12R")
      (libsource (lib "eagle-import") (part "TPTP12R"))
    )
    (comp (ref "C14")
      (value "22nF")
      (footprint "eagle-import:0603")
      (fields (field (name "PARTNO") "GRM188R71E223KA01D"))
      (libsource (lib "eagle-import") (part "CAPACITOR0603"))
    )
    (comp (ref "C15")
      (value "91pF")
      (footprint "eagle-import:0603")
      (fields (field (name "PARTNO") "GRM1885C2A910JA01D"))
      (libsource (lib "eagle-import") (part "CAPACITOR0603"))
    )
    (comp (ref "C16")
      (value "22nF")
      (footprint "eagle-import:0603")
      (fields (field (name "PARTNO") "GRM188R71E223KA01D"))
      (libsource (lib "eagle-import") (part "CAPACITOR0603"))
    )
    (comp (ref "C17")
      (value "91pF")
      (footprint "eagle-import:0603")
      (fields (field (name "PARTNO") "GRM1885C2A910JA01D"))
      (libsource (lib "eagle-import") (part "CAPACITOR0603"))
    )
    (comp (ref "C21")
      (value "470pF")
      (footprint "eagle-import:0603")
      (fields (field (name "PARTNO") "GRM1885C1H471JA01D"))
      (libsource (lib "eagle-import") (part "CAPACITOR0603"))
    )
    (comp (ref "C22")
      (value "20pF")
      (footprint "eagle-import:0603")
      (fields (field (name "PARTNO") "GRM1885C1H200JA01D"))
      (libsource (lib "eagle-import") (part "CAPACITOR0603"))
    )
    (comp (ref "C23")
      (value "16pF")
      (footprint "eagle-import:0603")
      (fields (field (name "PARTNO") "GCM1885C2A160JA16D"))
      (libsource (lib "eagle-import") (part "CAPACITOR0603"))
    )
    (comp (ref "C24")
      (value "24pF")
      (footprint "eagle-import:0603")
      (fields (field (name "PARTNO") "GRM1885C2A240JA01D"))
      (libsource (lib "eagle-import") (part "CAPACITOR0603"))
    )
    (comp (ref "C25")
      (value "24pF")
      (footprint "eagle-import:0603")
      (fields (field (name "PARTNO") "GRM1885C2A240JA01D"))
      (libsource (lib "eagle-import") (part "CAPACITOR0603"))
    )
    (comp (ref "C32")
      (value "2.2uF")
      (footprint "eagle-import:0603")
      (fields (field (name "PARTNO") "EMK107BJ225KA-T"))
      (libsource (lib "eagle-import") (part "CAPACITOR0603"))
    )
    (comp (ref "C34")
      (value "2.2uF")
      (footprint "eagle-import:0603")
      (fields (field (name "PARTNO") "EMK107BJ225KA-T"))
      (libsource (lib "eagle-import") (part "CAPACITOR0603"))
    )
    (comp (ref "L1")
      (value "47nH")
      (footprint "eagle-import:0603")
      (fields (field (name "PARTNO") "LQW18AN47NG00D"))
      (libsource (lib "eagle-import") (part "INDUCTOR0603"))
    )
    (comp (ref "L5")
      (value "470nH")
      (footprint "eagle-import:0603")
      (fields (field (name "PARTNO") "HK1608R47J-T"))
      (libsource (lib "eagle-import") (part "INDUCTOR0603"))
    )
    (comp (ref "L6")
      (value "130nH")
      (footprint "eagle-import:0603")
      (fields (field (name "PARTNO") "LQW18ANR13J00D"))
      (libsource (lib "eagle-import") (part "INDUCTOR0603"))
    )
    (comp (ref "L7")
      (value "100nH")
      (footprint "eagle-import:0603")
      (fields (field (name "PARTNO") "LQW18ANR10G00D"))
      (libsource (lib "eagle-import") (part "INDUCTOR0603"))
    )
    (comp (ref "L11")
      (value "56nH")
      (footprint "eagle-import:0603")
      (fields (field (name "PARTNO") "LQW18AN56NG00D"))
      (libsource (lib "eagle-import") (part "INDUCTOR0603"))
    )
    (comp (ref "R22")
      (value "22R")
      (footprint "eagle-import:0603")
      (fields (field (name "PARTNO") "RC0603JR-0722RL"))
      (libsource (lib "eagle-import") (part "RESISTOR0603"))
    )
    (comp (ref "U11")
      (value "SI4463")
      (footprint "eagle-import:SI4463")
      (fields (field (name "PARTNO") "SI4463-C2A-GMR"))
      (libsource (lib "eagle-import") (part "SI4463"))
    )
    (comp (ref "U12")
      (value "SI4463")
      (footprint "eagle-import:SI4463")
      (fields (field (name "PARTNO") "SI4463-C2A-GMR"))
      (libsource (lib "eagle-import") (part "SI4463"))
    )
    (comp (ref "X1")
      (value "CX3225SB30000D0FPLCC")
      (footprint "eagle-import:NX3225")
      (libsource (lib "eagle-import") (part "XTAL-4-3225"))
    )
    (comp (ref "X2")
      (value "CX3225SB30000D0FPLCC")
      (footprint "eagle-import:NX3225")
      (libsource (lib "eagle-import") (part "XTAL-4-3225"))
    )
  )
  (nets
    (net (code "1") (name "3.3V") (class "Default")
      (node (ref "3V3") (pin "TP") (pinfunction "TP_TP") (pintype "input"))
      (node (ref "C1") (pin "P$1") (pinfunction "1_P$1") (pintype "passive"))
      (node (ref "C14") (pin "P$1") (pinfunction "1_P$1") (pintype "passive"))
      (node (ref "C15") (pin "P$1") (pinfunction "1_P$1") (pintype "passive"))
      (node (ref "C16") (pin "P$1") (pinfunction "1_P$1") (pintype "passive"))
      (node (ref "C17") (pin "P$1") (pinfunction "1_P$1") (pintype "passive"))
      (node (ref "C26") (pin "P$1") (pinfunction "1_P$1") (pintype "passive"))
      (node (ref "C27") (pin "P$1") (pinfunction "1_P$1") (pintype "passive"))
      (node (ref "C28") (pin "P$1") (pinfunction "1_P$1") (pintype "passive"))
      (node (ref "C3") (pin "P$1") (pinfunction "1_P$1") (pintype "passive"))
      (node (ref "C32") (pin "P$1") (pinfunction "1_P$1") (pintype "passive"))
      (node (ref "C34") (pin "P$1") (pinfunction "1_P$1") (pintype "passive"))
      (node (ref "C46") (pin "P$1") (pinfunction "1_P$1") (pintype "passive"))
      (node (ref "C5") (pin "P$1") (pinfunction "1_P$1") (pintype "passive"))
      (node (ref "JLINK") (pin "5") (pinfunction "5_5") (pintype "passive"))
      (node (ref "L12") (pin "P$2") (pinfunction "2_P$2") (pintype "passive"))
      (node (ref "R1") (pin "P$2") (pinfunction "P$2_P$2") (pintype "passive"))
      (node (ref "R16") (pin "P$2") (pinfunction "P$2_P$2") (pintype "passive"))
      (node (ref "R22") (pin "P$2") (pinfunction "P$2_P$2") (pintype "passive"))
      (node (ref "U1") (pin "1") (pinfunction "FB_1") (pintype "bidirectional"))
      (node (ref "U11") (pin "6") (pinfunction "VDD_1_6") (pintype "power_in"))
      (node (ref "U11") (pin "8") (pinfunction "VDD_2_8") (pintype "power_in"))
      (node (ref "U12") (pin "6") (pinfunction "VDD_1_6") (pintype "power_in"))
      (node (ref "U12") (pin "8") (pinfunction "VDD_2_8") (pintype "power_in"))
      (node (ref "U13") (pin "1") (pinfunction "VDD_1") (pintype "bidirectional"))
      (node (ref "U13") (pin "17") (pinfunction "VDD_17") (pintype "bidirectional"))
      (node (ref "U13") (pin "5") (pinfunction "VDDA_5") (pintype "bidirectional"))
      (node (ref "U15") (pin "P$8") (pinfunction "EN_P$8") (pintype "bidirectional"))
      (node (ref "U15") (pin "P$9") (pinfunction "VCC_P$9") (pintype "bidirectional"))
      (node (ref "U2") (pin "P$6") (pinfunction "VBAT_P$6") (pintype "bidirectional"))
      (node (ref "U2") (pin "P$8") (pinfunction "VCC_P$8") (pintype "bidirectional"))
      (node (ref "U6") (pin "4") (pinfunction "VCC_4") (pintype "bidirectional"))
      (node (ref "U8") (pin "4") (pinfunction "S_4") (pintype "passive"))
    )
    (net (code "2") (name "BOOT0") (class "Default")
      (node (ref "R23") (pin "P$1") (pinfunction "P$1_P$1") (pintype "passive"))
      (node (ref "U13") (pin "31") (pinfunction "BOOT0_31") (pintype "bidirectional"))
    )
    (net (code "3") (name "CS1") (class "Default")
      (node (ref "U11") (pin "15") (pinfunction "NSEL_15") (pintype "input"))
      (node (ref "U13") (pin "10") (pinfunction "PA4_10") (pintype "bidirectional"))
    )
    (net (code "4") (name "CS2") (class "Default")
      (node (ref "U12") (pin "15") (pinfunction "NSEL_15") (pintype "input"))
      (node (ref "U13") (pin "6") (pinfunction "PA0_6") (pintype "bidirectional"))
    )
    (net (code "5") (name "GND") (class "Default")
      (node (ref "C1") (pin "P$2") (pinfunction "2_P$2") (pintype "passive"))
      (node (ref "C11") (pin "P$2") (pinfunction "2_P$2") (pintype "passive"))
      (node (ref "C13") (pin "P$2") (pinfunction "2_P$2") (pintype "passive"))
      (node (ref "C14") (pin "P$2") (pinfunction "2_P$2") (pintype "passive"))
      (node (ref "C15") (pin "P$2") (pinfunction "2_P$2") (pintype "passive"))
      (node (ref "C16") (pin "P$2") (pinfunction "2_P$2") (pintype "passive"))
      (node (ref "C17") (pin "P$2") (pinfunction "2_P$2") (pintype "passive"))
      (node (ref "C21") (pin "P$2") (pinfunction "2_P$2") (pintype "passive"))
      (node (ref "C23") (pin "P$2") (pinfunction "2_P$2") (pintype "passive"))
      (node (ref "C24") (pin "P$2") (pinfunction "2_P$2") (pintype "passive"))
      (node (ref "C25") (pin "P$2") (pinfunction "2_P$2") (pintype "passive"))
      (node (ref "C26") (pin "P$2") (pinfunction "2_P$2") (pintype "passive"))
      (node (ref "C27") (pin "P$2") (pinfunction "2_P$2") (pintype "passive"))
      (node (ref "C28") (pin "P$2") (pinfunction "2_P$2") (pintype "passive"))
      (node (ref "C3") (pin "P$2") (pinfunction "2_P$2") (pintype "passive"))
      (node (ref "C30") (pin "P$2") (pinfunction "2_P$2") (pintype "passive"))
      (node (ref "C32") (pin "P$2") (pinfunction "2_P$2") (pintype "passive"))
      (node (ref "C34") (pin "P$2") (pinfunction "2_P$2") (pintype "passive"))
      (node (ref "C36") (pin "P$2") (pinfunction "2_P$2") (pintype "passive"))
      (node (ref "C37") (pin "P$2") (pinfunction "2_P$2") (pintype "passive"))
      (node (ref "C39") (pin "P$2") (pinfunction "2_P$2") (pintype "passive"))
      (node (ref "C4") (pin "P$2") (pinfunction "2_P$2") (pintype "passive"))
      (node (ref "C42") (pin "P$2") (pinfunction "2_P$2") (pintype "passive"))
      (node (ref "C43") (pin "P$2") (pinfunction "2_P$2") (pintype "passive"))
      (node (ref "C46") (pin "P$2") (pinfunction "2_P$2") (pintype "passive"))
      (node (ref "C47") (pin "P$2") (pinfunction "2_P$2") (pintype "passive"))
      (node (ref "C49") (pin "P$2") (pinfunction "2_P$2") (pintype "passive"))
      (node (ref "C5") (pin "P$2") (pinfunction "2_P$2") (pintype "passive"))
      (node (ref "C52") (pin "P$2") (pinfunction "2_P$2") (pintype "passive"))
      (node (ref "C53") (pin "P$2") (pinfunction "2_P$2") (pintype "passive"))
      (node (ref "C6") (pin "P$2") (pinfunction "2_P$2") (pintype "passive"))
      (node (ref "C7") (pin "P$2") (pinfunction "2_P$2") (pintype "passive"))
      (node (ref "C8") (pin "P$2") (pinfunction "2_P$2") (pintype "passive"))
      (node (ref "GND1") (pin "TP") (pinfunction "TP_TP") (pintype "input"))
      (node (ref "GND2") (pin "TP") (pinfunction "TP_TP") (pintype "input"))
      (node (ref "J$1") (pin "GND@0") (pinfunction "GND_GND@0") (pintype "bidirectional"))
      (node (ref "J$1") (pin "GND@1") (pinfunction "GND_GND@1") (pintype "bidirectional"))
      (node (ref "J$1") (pin "GND@2") (pinfunction "GND_GND@2") (pintype "bidirectional"))
      (node (ref "J$1") (pin "GND@3") (pinfunction "GND_GND@3") (pintype "bidirectional"))
      (node (ref "JLINK") (pin "1") (pinfunction "1_1") (pintype "passive"))
      (node (ref "JP2") (pin "7") (pinfunction "7_7") (pintype "bidirectional"))
      (node (ref "L14") (pin "P$1") (pinfunction "1_P$1") (pintype "passive"))
      (node (ref "Q1") (pin "1") (pinfunction "G_1") (pintype "passive"))
      (node (ref "R12") (pin "P$1") (pinfunction "P$1_P$1") (pintype "passive"))
      (node (ref "R23") (pin "P$2") (pinfunction "P$2_P$2") (pintype "passive"))
      (node (ref "R4") (pin "P$1") (pinfunction "P$1_P$1") (pintype "passive"))
      (node (ref "R7") (pin "P$2") (pinfunction "P$2_P$2") (pintype "passive"))
      (node (ref "R9") (pin "P$1") (pinfunction "P$1_P$1") (pintype "passive"))
      (node (ref "S1") (pin "P$2") (pinfunction "S2_P$2") (pintype "bidirectional"))
      (node (ref "TP2") (pin "TP") (pinfunction "TP_TP") (pintype "input"))
      (node (ref "TP3") (pin "TP") (pinfunction "TP_TP") (pintype "input"))
      (node (ref "TP4") (pin "TP") (pinfunction "TP_TP") (pintype "input"))
      (node (ref "TP5") (pin "TP") (pinfunction "TP_TP") (pintype "input"))
      (node (ref "TP6") (pin "TP") (pinfunction "TP_TP") (pintype "input"))
      (node (ref "TP7") (pin "TP") (pinfunction "TP_TP") (pintype "input"))
      (node (ref "TP8") (pin "TP") (pinfunction "TP_TP") (pintype "input"))
      (node (ref "TP9") (pin "TP") (pinfunction "TP_TP") (pintype "input"))
      (node (ref "U1") (pin "4") (pinfunction "GND_4") (pintype "bidirectional"))
      (node (ref "U11") (pin "18") (pinfunction "GNDX_18") (pintype "bidirectional"))
      (node (ref "U11") (pin "3") (pinfunction "RXN_3") (pintype "input"))
      (node (ref "U11") (pin "5") (pinfunction "NC_5") (pintype "bidirectional"))
      (node (ref "U11") (pin "EXP") (pinfunction "PAD_EXP") (pintype "bidirectional"))
      (node (ref "U12") (pin "18") (pinfunction "GNDX_18") (pintype "bidirectional"))
      (node (ref "U12") (pin "3") (pinfunction "RXN_3") (pintype "input"))
      (node (ref "U12") (pin "5") (pinfunction "NC_5") (pintype "bidirectional"))
      (node (ref "U12") (pin "EXP") (pinfunction "PAD_EXP") (pintype "bidirectional"))
      (node (ref "U13") (pin "16") (pinfunction "VSS_16") (pintype "bidirectional"))
      (node (ref "U13") (pin "32") (pinfunction "VSS_32") (pintype "bidirectional"))
      (node (ref "U13") (pin "EXP") (pinfunction "PAD_EXP") (pintype "bidirectional"))
      (node (ref "U15") (pin "P$1") (pinfunction "GND_P$1") (pintype "bidirectional"))
      (node (ref "U15") (pin "P$10") (pinfunction "GND_P$10") (pintype "bidirectional"))
      (node (ref "U15") (pin "P$12") (pinfunction "GND_P$12") (pintype "bidirectional"))
      (node (ref "U15") (pin "P$13") (pinfunction "GND_P$13") (pintype "bidirectional"))
      (node (ref "U15") (pin "P$3") (pinfunction "GND_P$3") (pintype "bidirectional"))
      (node (ref "U15") (pin "P$4") (pinfunction "GND_P$4") (pintype "bidirectional"))
      (node (ref "U15") (pin "P$6") (pinfunction "GND_P$6") (pintype "bidirectional"))
      (node (ref "U2") (pin "P$1") (pinfunction "GND_P$1") (pintype "bidirectional"))
      (node (ref "U2") (pin "P$10") (pinfunction "GND_P$10") (pintype "bidirectional"))
      (node (ref "U2") (pin "P$12") (pinfunction "GND_P$12") (pintype "bidirectional"))
      (node (ref "U3") (pin "P$4") (pinfunction "GND_P$4") (pintype "bidirectional"))
      (node (ref "U3") (pin "P$7") (pinfunction "GND_P$7") (pintype "bidirectional"))
      (node (ref "U4") (pin "4") (pinfunction "S_4") (pintype "bidirectional"))
      (node (ref "U5") (pin "2") (pinfunction "GND_2") (pintype "bidirectional"))
      (node (ref "U5") (pin "4") (pinfunction "GND_4") (pintype "bidirectional"))
      (node (ref "U5") (pin "5") (pinfunction "GND_5") (pintype "bidirectional"))
      (node (ref "U6") (pin "2") (pinfunction "GND_2") (pintype "bidirectional"))
      (node (ref "U6") (pin "5") (pinfunction "WP_5") (pintype "bidirectional"))
      (node (ref "U7") (pin "2") (pinfunction "S_2") (pintype "passive"))
      (node (ref "U7") (pin "2@1") (pinfunction "PAD_2@1") (pintype "bidirectional"))
      (node (ref "U8") (pin "1") (pinfunction "S_1") (pintype "bidirectional"))
      (node (ref "X1") (pin "2") (pinfunction "G2_2") (pintype "power_in"))
      (node (ref "X1") (pin "4") (pinfunction "G1_4") (pintype "power_in"))
      (node (ref "X2") (pin "2") (pinfunction "G2_2") (pintype "power_in"))
      (node (ref "X2") (pin "4") (pinfunction "G1_4") (pintype "power_in"))
    )
    (net (code "6") (name "GPS_1PPS") (class "Default")
      (node (ref "U2") (pin "P$4") (pinfunction "1PPS_P$4") (pintype "bidirectional"))
      (node (ref "U4") (pin "5") (pinfunction "G_5") (pintype "bidirectional"))
    )
    (net (code "7") (name "GPS_EN") (class "Default")
      (node (ref "R3") (pin "P$2") (pinfunction "P$2_P$2") (pintype "passive"))
      (node (ref "R6") (pin "P$2") (pinfunction "P$2_P$2") (pintype "passive"))
      (node (ref "R7") (pin "P$1") (pinfunction "P$1_P$1") (pintype "passive"))
      (node (ref "U13") (pin "2") (pinfunction "OSC_IN/PC14_2") (pintype "bidirectional"))
      (node (ref "U4") (pin "2") (pinfunction "G_2") (pintype "bidirectional"))
    )
    (net (code "8") (name "GPS_STATUS") (class "Default")
      (node (ref "JP2") (pin "4") (pinfunction "4_4") (pintype "bidirectional"))
      (node (ref "U13") (pin "21") (pinfunction "PA11_21") (pintype "bidirectional"))
    )
    (net (code "9") (name "GPS_UART_TX") (class "Default")
      (node (ref "R3") (pin "P$1") (pinfunction "P$1_P$1") (pintype "passive"))
      (node (ref "U2") (pin "P$2") (pinfunction "TX_P$2") (pintype "bidirectional"))
      (node (ref "U4") (pin "1") (pinfunction "S_1") (pintype "bidirectional"))
    )
    (net (code "10") (name "I2C_SCL") (class "Default")
      (node (ref "U13") (pin "29") (pinfunction "PB6_29") (pintype "bidirectional"))
      (node (ref "U6") (pin "1") (pinfunction "SCL_1") (pintype "bidirectional"))
    )
    (net (code "11") (name "I2C_SDA") (class "Default")
      (node (ref "U13") (pin "30") (pinfunction "PB7_30") (pintype "bidirectional"))
      (node (ref "U6") (pin "3") (pinfunction "SDA_3") (pintype "bidirectional"))
    )
    (net (code "12") (name "MCU_GPS_1PPS") (class "Default")
      (node (ref "R6") (pin "P$1") (pinfunction "P$1_P$1") (pintype "passive"))
      (node (ref "U13") (pin "8") (pinfunction "PA2_8") (pintype "bidirectional"))
      (node (ref "U4") (pin "3") (pinfunction "D_3") (pintype "bidirectional"))
    )
    (net (code "13") (name "MCU_GPS_UART_RX") (class "Default")
      (node (ref "R16") (pin "P$1") (pinfunction "P$1_P$1") (pintype "passive"))
      (node (ref "U13") (pin "9") (pinfunction "PA3_9") (pintype "bidirectional"))
      (node (ref "U4") (pin "6") (pinfunction "D_6") (pintype "bidirectional"))
    )
    (net (code "14") (name "MCU_UART_RX") (class "Default")
      (node (ref "JP2") (pin "3") (pinfunction "3_3") (pintype "bidirectional"))
      (node (ref "RX") (pin "TP") (pinfunction "TP_TP") (pintype "input"))
      (node (ref "U13") (pin "20") (pinfunction "PA10_20") (pintype "bidirectional"))
    )
    (net (code "15") (name "MCU_UART_TX") (class "Default")
      (node (ref "JP2") (pin "5") (pinfunction "5_5") (pintype "bidirectional"))
      (node (ref "TX") (pin "TP") (pinfunction "TP_TP") (pintype "input"))
      (node (ref "U13") (pin "19") (pinfunction "PA9_19") (pintype "bidirectional"))
    )
    (net (code "16") (name "MISO") (class "Default")
      (node (ref "U11") (pin "13") (pinfunction "SDO_13") (pintype "output"))
      (node (ref "U12") (pin "13") (pinfunction "SDO_13") (pintype "output"))
      (node (ref "U13") (pin "12") (pinfunction "PA6_12") (pintype "bidirectional"))
    )
    (net (code "17") (name "MOSI") (class "Default")
      (node (ref "U11") (pin "14") (pinfunction "SDI_14") (pintype "input"))
      (node (ref "U12") (pin "14") (pinfunction "SDI_14") (pintype "input"))
      (node (ref "U13") (pin "13") (pinfunction "PA7_13") (pintype "bidirectional"))
    )
    (net (code "18") (name "NRST") (class "Default")
      (node (ref "JLINK") (pin "2") (pinfunction "2_2") (pintype "passive"))
      (node (ref "NRST") (pin "TP") (pinfunction "TP_TP") (pintype "input"))
      (node (ref "S1") (pin "P$1") (pinfunction "S1_P$1") (pintype "bidirectional"))
      (node (ref "U13") (pin "4") (pinfunction "NRST_4") (pintype "bidirectional"))
    )
    (net (code "19") (name "Net-(C2-1)") (class "Default")
      (node (ref "C2") (pin "P$1") (pinfunction "1_P$1") (pintype "passive"))
      (node (ref "U1") (pin "6") (pinfunction "BST_6") (pintype "bidirectional"))
    )
    (net (code "20") (name "Net-(C2-2)") (class "Default")
      (node (ref "C2") (pin "P$2") (pinfunction "2_P$2") (pintype "passive"))
      (node (ref "L12") (pin "P$1") (pinfunction "1_P$1") (pintype "passive"))
      (node (ref "U1") (pin "5") (pinfunction "SW_5") (pintype "bidirectional"))
    )
    (net (code "21") (name "Net-(C9-1)") (class "Default")
      (node (ref "C9") (pin "P$1") (pinfunction "1_P$1") (pintype "passive"))
      (node (ref "L8") (pin "P$2") (pinfunction "2_P$2") (pintype "passive"))
    )
    (net (code "22") (name "Net-(C10-1)") (class "Default")
      (node (ref "C10") (pin "P$1") (pinfunction "1_P$1") (pintype "passive"))
      (node (ref "C8") (pin "P$1") (pinfunction "1_P$1") (pintype "passive"))
      (node (ref "C9") (pin "P$2") (pinfunction "2_P$2") (pintype "passive"))
      (node (ref "L14") (pin "P$2") (pinfunction "2_P$2") (pintype "passive"))
    )
    (net (code "23") (name "Net-(C10-2)") (class "Default")
      (node (ref "C10") (pin "P$2") (pinfunction "2_P$2") (pintype "passive"))
      (node (ref "L13") (pin "P$1") (pinfunction "1_P$1") (pintype "passive"))
    )
    (net (code "24") (name "Net-(C11-1)") (class "Default")
      (node (ref "C11") (pin "P$1") (pinfunction "1_P$1") (pintype "passive"))
      (node (ref "L17") (pin "P$2") (pinfunction "2_P$2") (pintype "passive"))
      (node (ref "R11") (pin "P$1") (pinfunction "P$1_P$1") (pintype "passive"))
      (node (ref "R12") (pin "P$2") (pinfunction "P$2_P$2") (pintype "passive"))
    )
    (net (code "25") (name "Net-(C12-1)") (class "Default")
      (node (ref "C12") (pin "P$1") (pinfunction "1_P$1") (pintype "passive"))
      (node (ref "L13") (pin "P$2") (pinfunction "2_P$2") (pintype "passive"))
    )
    (net (code "26") (name "Net-(C12-2)") (class "Default")
      (node (ref "C12") (pin "P$2") (pinfunction "2_P$2") (pintype "passive"))
      (node (ref "U5") (pin "6") (pinfunction "IN_6") (pintype "bidirectional"))
    )
    (net (code "27") (name "Net-(C13-1)") (class "Default")
      (node (ref "C13") (pin "P$1") (pinfunction "1_P$1") (pintype "passive"))
      (node (ref "R10") (pin "P$2") (pinfunction "P$2_P$2") (pintype "passive"))
      (node (ref "U5") (pin "1") (pinfunction "VCC_1") (pintype "bidirectional"))
    )
    (net (code "28") (name "Net-(C18-1)") (class "Default")
      (node (ref "C18") (pin "P$1") (pinfunction "1_P$1") (pintype "passive"))
      (node (ref "U5") (pin "3") (pinfunction "OUT_3") (pintype "bidirectional"))
    )
    (net (code "29") (name "Net-(C21-1)") (class "Default")
      (node (ref "C21") (pin "P$1") (pinfunction "1_P$1") (pintype "passive"))
      (node (ref "L5") (pin "P$1") (pinfunction "1_P$1") (pintype "passive"))
      (node (ref "R22") (pin "P$1") (pinfunction "P$1_P$1") (pintype "passive"))
    )
    (net (code "30") (name "Net-(C22-1)") (class "Default")
      (node (ref "C22") (pin "P$1") (pinfunction "1_P$1") (pintype "passive"))
      (node (ref "L5") (pin "P$2") (pinfunction "2_P$2") (pintype "passive"))
      (node (ref "U11") (pin "4") (pinfunction "TX_4") (pintype "output"))
    )
    (net (code "31") (name "Net-(C22-2)") (class "Default")
      (node (ref "C22") (pin "P$2") (pinfunction "2_P$2") (pintype "passive"))
      (node (ref "L1") (pin "P$1") (pinfunction "1_P$1") (pintype "passive"))
    )
    (net (code "32") (name "Net-(C23-1)") (class "Default")
      (node (ref "C23") (pin "P$1") (pinfunction "1_P$1") (pintype "passive"))
      (node (ref "L1") (pin "P$2") (pinfunction "2_P$2") (pintype "passive"))
      (node (ref "L6") (pin "P$1") (pinfunction "1_P$1") (pintype "passive"))
    )
    (net (code "33") (name "Net-(C24-1)") (class "Default")
      (node (ref "C24") (pin "P$1") (pinfunction "1_P$1") (pintype "passive"))
      (node (ref "L6") (pin "P$2") (pinfunction "2_P$2") (pintype "passive"))
      (node (ref "L7") (pin "P$1") (pinfunction "1_P$1") (pintype "passive"))
    )
    (net (code "34") (name "Net-(C25-1)") (class "Default")
      (node (ref "C25") (pin "P$1") (pinfunction "1_P$1") (pintype "passive"))
      (node (ref "L11") (pin "P$1") (pinfunction "1_P$1") (pintype "passive"))
      (node (ref "L7") (pin "P$2") (pinfunction "2_P$2") (pintype "passive"))
    )
    (net (code "35") (name "Net-(C29-2)") (class "Default")
      (node (ref "C29") (pin "P$2") (pinfunction "2_P$2") (pintype "passive"))
      (node (ref "C30") (pin "P$1") (pinfunction "1_P$1") (pintype "passive"))
      (node (ref "L3") (pin "P$1") (pinfunction "1_P$1") (pintype "passive"))
    )
    (net (code "36") (name "Net-(C36-1)") (class "Default")
      (node (ref "C36") (pin "P$1") (pinfunction "1_P$1") (pintype "passive"))
      (node (ref "L10") (pin "P$1") (pinfunction "1_P$1") (pintype "passive"))
      (node (ref "L9") (pin "P$2") (pinfunction "2_P$2") (pintype "passive"))
    )
    (net (code "37") (name "Net-(C37-1)") (class "Default")
      (node (ref "C37") (pin "P$1") (pinfunction "1_P$1") (pintype "passive"))
      (node (ref "C39") (pin "P$1") (pinfunction "1_P$1") (pintype "passive"))
      (node (ref "L4") (pin "P$2") (pinfunction "2_P$2") (pintype "passive"))
      (node (ref "L9") (pin "P$1") (pinfunction "1_P$1") (pintype "passive"))
      (node (ref "U7") (pin "3") (pinfunction "D_3") (pintype "passive"))
    )
    (net (code "38") (name "Net-(C42-1)") (class "Default")
      (node (ref "C42") (pin "P$1") (pinfunction "1_P$1") (pintype "passive"))
      (node (ref "C52") (pin "P$1") (pinfunction "1_P$1") (pintype "passive"))
      (node (ref "L10") (pin "P$2") (pinfunction "2_P$2") (pintype "passive"))
      (node (ref "L23") (pin "P$1") (pinfunction "1_P$1") (pintype "passive"))
    )
    (net (code "39") (name "Net-(C43-1)") (class "Default")
      (node (ref "C43") (pin "P$1") (pinfunction "1_P$1") (pintype "passive"))
      (node (ref "C6") (pin "P$1") (pinfunction "1_P$1") (pintype "passive"))
      (node (ref "L2") (pin "P$2") (pinfunction "2_P$2") (pintype "passive"))
      (node (ref "U1") (pin "2") (pinfunction "EN_2") (pintype "bidirectional"))
      (node (ref "U1") (pin "3") (pinfunction "VIN_3") (pintype "bidirectional"))
    )
    (net (code "40") (name "Net-(C44-1)") (class "Default")
      (node (ref "C44") (pin "P$1") (pinfunction "1_P$1") (pintype "passive"))
      (node (ref "C53") (pin "P$1") (pinfunction "1_P$1") (pintype "passive"))
      (node (ref "L23") (pin "P$2") (pinfunction "2_P$2") (pintype "passive"))
    )
    (net (code "41") (name "Net-(J$1-SIGNAL)") (class "Default")
      (node (ref "J$1") (pin "SIG") (pinfunction "SIGNAL_SIG") (pintype "bidirectional"))
      (node (ref "TP1") (pin "TP") (pinfunction "TP_TP") (pintype "input"))
      (node (ref "U15") (pin "P$2") (pinfunction "RF1_P$2") (pintype "bidirectional"))
    )
    (net (code "42") (name "Net-(L17-1)") (class "Default")
      (node (ref "L17") (pin "P$1") (pinfunction "1_P$1") (pintype "passive"))
      (node (ref "L3") (pin "P$2") (pinfunction "2_P$2") (pintype "passive"))
      (node (ref "U7") (pin "1") (pinfunction "G_1") (pintype "passive"))
    )
    (net (code "43") (name "Net-(Q1-D)") (class "Default")
      (node (ref "F1") (pin "2") (pinfunction "2_2") (pintype "bidirectional"))
      (node (ref "Q1") (pin "3") (pinfunction "D_3") (pintype "passive"))
      (node (ref "V_BAT") (pin "TP") (pinfunction "TP_TP") (pintype "input"))
    )
    (net (code "44") (name "Net-(U3-ADJ)") (class "Default")
      (node (ref "R4") (pin "P$2") (pinfunction "P$2_P$2") (pintype "passive"))
      (node (ref "R5") (pin "P$1") (pinfunction "P$1_P$1") (pintype "passive"))
      (node (ref "U3") (pin "P$2") (pinfunction "ADJ_P$2") (pintype "bidirectional"))
    )
    (net (code "45") (name "Net-(U8A-D)") (class "Default")
      (node (ref "R1") (pin "P$1") (pinfunction "P$1_P$1") (pintype "passive"))
      (node (ref "U8") (pin "5") (pinfunction "G_5") (pintype "passive"))
      (node (ref "U8") (pin "6") (pinfunction "D_6") (pintype "bidirectional"))
    )
    (net (code "46") (name "Net-(U10-RF)") (class "Default")
      (node (ref "U10") (pin "P$1") (pinfunction "RF_P$1") (pintype "bidirectional"))
      (node (ref "U2") (pin "P$11") (pinfunction "RFIN_P$11") (pintype "bidirectional"))
    )
    (net (code "47") (name "Net-(U11-XIN)") (class "Default")
      (node (ref "U11") (pin "17") (pinfunction "XIN_17") (pintype "input"))
      (node (ref "X1") (pin "3") (pinfunction "X2_3") (pintype "bidirectional"))
    )
    (net (code "48") (name "Net-(U11-XOUT)") (class "Default")
      (node (ref "U11") (pin "16") (pinfunction "XOUT_16") (pintype "bidirectional"))
      (node (ref "X1") (pin "1") (pinfunction "X1_1") (pintype "bidirectional"))
    )
    (net (code "49") (name "Net-(U12-XIN)") (class "Default")
      (node (ref "U12") (pin "17") (pinfunction "XIN_17") (pintype "input"))
      (node (ref "X2") (pin "3") (pinfunction "X2_3") (pintype "bidirectional"))
    )
    (net (code "50") (name "Net-(U12-XOUT)") (class "Default")
      (node (ref "U12") (pin "16") (pinfunction "XOUT_16") (pintype "bidirectional"))
      (node (ref "X2") (pin "1") (pinfunction "X1_1") (pintype "bidirectional"))
    )
    (net (code "51") (name "Net-(U15-CTRL)") (class "Default")
      (node (ref "R8") (pin "P$1") (pinfunction "P$1_P$1") (pintype "passive"))
      (node (ref "R9") (pin "P$2") (pinfunction "P$2_P$2") (pintype "passive"))
      (node (ref "U15") (pin "P$7") (pinfunction "CTRL_P$7") (pintype "bidirectional"))
    )
    (net (code "52") (name "PA_IN") (class "Default")
      (node (ref "C29") (pin "P$1") (pinfunction "1_P$1") (pintype "passive"))
      (node (ref "L11") (pin "P$2") (pinfunction "2_P$2") (pintype "passive"))
    )
    (net (code "53") (name "PA_OUT") (class "Default")
      (node (ref "C44") (pin "P$2") (pinfunction "2_P$2") (pintype "passive"))
      (node (ref "U15") (pin "P$5") (pinfunction "RF3_P$5") (pintype "bidirectional"))
    )
    (net (code "54") (name "RF_IN") (class "Default")
      (node (ref "L8") (pin "P$1") (pinfunction "1_P$1") (pintype "passive"))
      (node (ref "U15") (pin "P$11") (pinfunction "RF2_P$11") (pintype "bidirectional"))
    )
    (net (code "55") (name "RX_EN") (class "Default")
      (node (ref "R8") (pin "P$2") (pinfunction "P$2_P$2") (pintype "passive"))
      (node (ref "U11") (pin "20") (pinfunction "GPIO3_20") (pintype "bidirectional"))
      (node (ref "U8") (pin "2") (pinfunction "G_2") (pintype "bidirectional"))
    )
    (net (code "56") (name "RX_IC_CLK") (class "Default")
      (node (ref "U12") (pin "20") (pinfunction "GPIO3_20") (pintype "bidirectional"))
      (node (ref "U13") (pin "26") (pinfunction "PB3_26") (pintype "bidirectional"))
    )
    (net (code "57") (name "RX_IC_DATA") (class "Default")
      (node (ref "U12") (pin "10") (pinfunction "GPIO1_10") (pintype "bidirectional"))
      (node (ref "U13") (pin "27") (pinfunction "PB4_27") (pintype "bidirectional"))
    )
    (net (code "58") (name "RX_IN") (class "Default")
      (node (ref "C18") (pin "P$2") (pinfunction "2_P$2") (pintype "passive"))
      (node (ref "U11") (pin "2") (pinfunction "RXP_2") (pintype "input"))
      (node (ref "U12") (pin "2") (pinfunction "RXP_2") (pintype "input"))
    )
    (net (code "59") (name "RX_STATUS") (class "Default")
      (node (ref "JP2") (pin "6") (pinfunction "6_6") (pintype "bidirectional"))
      (node (ref "U13") (pin "7") (pinfunction "PA1_7") (pintype "bidirectional"))
    )
    (net (code "60") (name "SCK") (class "Default")
      (node (ref "U11") (pin "12") (pinfunction "SCLK_12") (pintype "input"))
      (node (ref "U12") (pin "12") (pinfunction "SCLK_12") (pintype "input"))
      (node (ref "U13") (pin "11") (pinfunction "PA5_11") (pintype "bidirectional"))
    )
    (net (code "61") (name "SDN1") (class "Default")
      (node (ref "U11") (pin "1") (pinfunction "SDN_1") (pintype "input"))
      (node (ref "U13") (pin "14") (pinfunction "PB0_14") (pintype "bidirectional"))
    )
    (net (code "62") (name "SDN2") (class "Default")
      (node (ref "U12") (pin "1") (pinfunction "SDN_1") (pintype "input"))
      (node (ref "U13") (pin "25") (pinfunction "PA15_25") (pintype "bidirectional"))
    )
    (net (code "63") (name "SWCLK") (class "Default")
      (node (ref "JLINK") (pin "3") (pinfunction "3_3") (pintype "passive"))
      (node (ref "SWCLK") (pin "TP") (pinfunction "TP_TP") (pintype "input"))
      (node (ref "U13") (pin "24") (pinfunction "PA14_24") (pintype "bidirectional"))
    )
    (net (code "64") (name "SWDIO") (class "Default")
      (node (ref "JLINK") (pin "4") (pinfunction "4_4") (pintype "passive"))
      (node (ref "SWDIO") (pin "TP") (pinfunction "TP_TP") (pintype "input"))
      (node (ref "U13") (pin "23") (pinfunction "PA13_23") (pintype "bidirectional"))
    )
    (net (code "65") (name "TRX_IC_CLOCK") (class "Default")
      (node (ref "U11") (pin "19") (pinfunction "GPIO2_19") (pintype "bidirectional"))
      (node (ref "U13") (pin "3") (pinfunction "OSC_OUT/PC15_3") (pintype "bidirectional"))
    )
    (net (code "66") (name "TRX_IC_DATA") (class "Default")
      (node (ref "U11") (pin "10") (pinfunction "GPIO1_10") (pintype "bidirectional"))
      (node (ref "U13") (pin "15") (pinfunction "PB1_15") (pintype "bidirectional"))
    )
    (net (code "67") (name "TX_DISABLE") (class "Default")
      (node (ref "JP2") (pin "2") (pinfunction "2_2") (pintype "bidirectional"))
      (node (ref "U13") (pin "22") (pinfunction "PA12_22") (pintype "bidirectional"))
    )
    (net (code "68") (name "TX_STATUS") (class "Default")
      (node (ref "JP2") (pin "8") (pinfunction "8_8") (pintype "bidirectional"))
      (node (ref "U13") (pin "18") (pinfunction "PA8_18") (pintype "bidirectional"))
    )
    (net (code "69") (name "V_IN") (class "Default")
      (node (ref "C4") (pin "P$1") (pinfunction "1_P$1") (pintype "passive"))
      (node (ref "C47") (pin "P$1") (pinfunction "1_P$1") (pintype "passive"))
      (node (ref "F1") (pin "1") (pinfunction "1_1") (pintype "bidirectional"))
      (node (ref "JP2") (pin "1") (pinfunction "1_1") (pintype "bidirectional"))
      (node (ref "L2") (pin "P$1") (pinfunction "1_P$1") (pintype "passive"))
      (node (ref "Q1") (pin "2") (pinfunction "S_2") (pintype "passive"))
      (node (ref "U3") (pin "P$5") (pinfunction "EN_P$5") (pintype "bidirectional"))
      (node (ref "U3") (pin "P$6") (pinfunction "VIN_P$6") (pintype "bidirectional"))
    )
    (net (code "70") (name "V_LNA") (class "Default")
      (node (ref "R10") (pin "P$1") (pinfunction "P$1_P$1") (pintype "passive"))
      (node (ref "U8") (pin "3") (pinfunction "D_3") (pintype "passive"))
    )
    (net (code "71") (name "V_PA") (class "Default")
      (node (ref "C49") (pin "P$1") (pinfunction "1_P$1") (pintype "passive"))
      (node (ref "C7") (pin "P$1") (pinfunction "1_P$1") (pintype "passive"))
      (node (ref "L4") (pin "P$1") (pinfunction "1_P$1") (pintype "passive"))
      (node (ref "R5") (pin "P$2") (pinfunction "P$2_P$2") (pintype "passive"))
      (node (ref "U3") (pin "P$1") (pinfunction "VOUT_P$1") (pintype "bidirectional"))
      (node (ref "V_PA") (pin "TP") (pinfunction "TP_TP") (pintype "input"))
    )
    (net (code "72") (name "V_PA_BIAS") (class "Default")
      (node (ref "R11") (pin "P$2") (pinfunction "P$2_P$2") (pintype "passive"))
      (node (ref "U13") (pin "28") (pinfunction "PB5_28") (pintype "bidirectional"))
    )
    (net (code "73") (name "unconnected-(S1-S1-PadP$4)") (class "Default")
      (node (ref "S1") (pin "P$4") (pinfunction "S1_P$4") (pintype "bidirectional"))
    )
    (net (code "74") (name "unconnected-(S1-S2-PadP$3)") (class "Default")
      (node (ref "S1") (pin "P$3") (pinfunction "S2_P$3") (pintype "bidirectional"))
    )
    (net (code "75") (name "unconnected-(U2-RX-PadP$3)") (class "Default")
      (node (ref "U2") (pin "P$3") (pinfunction "RX_P$3") (pintype "bidirectional"))
    )
    (net (code "76") (name "unconnected-(U3-PG-PadP$3)") (class "Default")
      (node (ref "U3") (pin "P$3") (pinfunction "PG_P$3") (pintype "bidirectional"))
    )
    (net (code "77") (name "unconnected-(U10-PAD-PadP$2)") (class "Default")
      (node (ref "U10") (pin "P$2") (pinfunction "PAD_P$2") (pintype "bidirectional"))
    )
    (net (code "78") (name "unconnected-(U11-GPIO0-Pad9)") (class "Default")
      (node (ref "U11") (pin "9") (pinfunction "GPIO0_9") (pintype "bidirectional"))
    )
    (net (code "79") (name "unconnected-(U11-NIRQ-Pad11)") (class "Default")
      (node (ref "U11") (pin "11") (pinfunction "NIRQ_11") (pintype "bidirectional"))
    )
    (net (code "80") (name "unconnected-(U11-TXRAMP-Pad7)") (class "Default")
      (node (ref "U11") (pin "7") (pinfunction "TXRAMP_7") (pintype "bidirectional"))
    )
    (net (code "81") (name "unconnected-(U12-GPIO0-Pad9)") (class "Default")
      (node (ref "U12") (pin "9") (pinfunction "GPIO0_9") (pintype "bidirectional"))
    )
    (net (code "82") (name "unconnected-(U12-GPIO2-Pad19)") (class "Default")
      (node (ref "U12") (pin "19") (pinfunction "GPIO2_19") (pintype "bidirectional"))
    )
    (net (code "83") (name "unconnected-(U12-NIRQ-Pad11)") (class "Default")
      (node (ref "U12") (pin "11") (pinfunction "NIRQ_11") (pintype "bidirectional"))
    )
    (net (code "84") (name "unconnected-(U12-TX-Pad4)") (class "Default")
      (node (ref "U12") (pin "4") (pinfunction "TX_4") (pintype "output"))
    )
    (net (code "85") (name "unconnected-(U12-TXRAMP-Pad7)") (class "Default")
      (node (ref "U12") (pin "7") (pinfunction "TXRAMP_7") (pintype "bidirectional"))
    )
  )
)
